# frontplatine_final.net
KiCad netlist of a schematic drawn in EAGLE
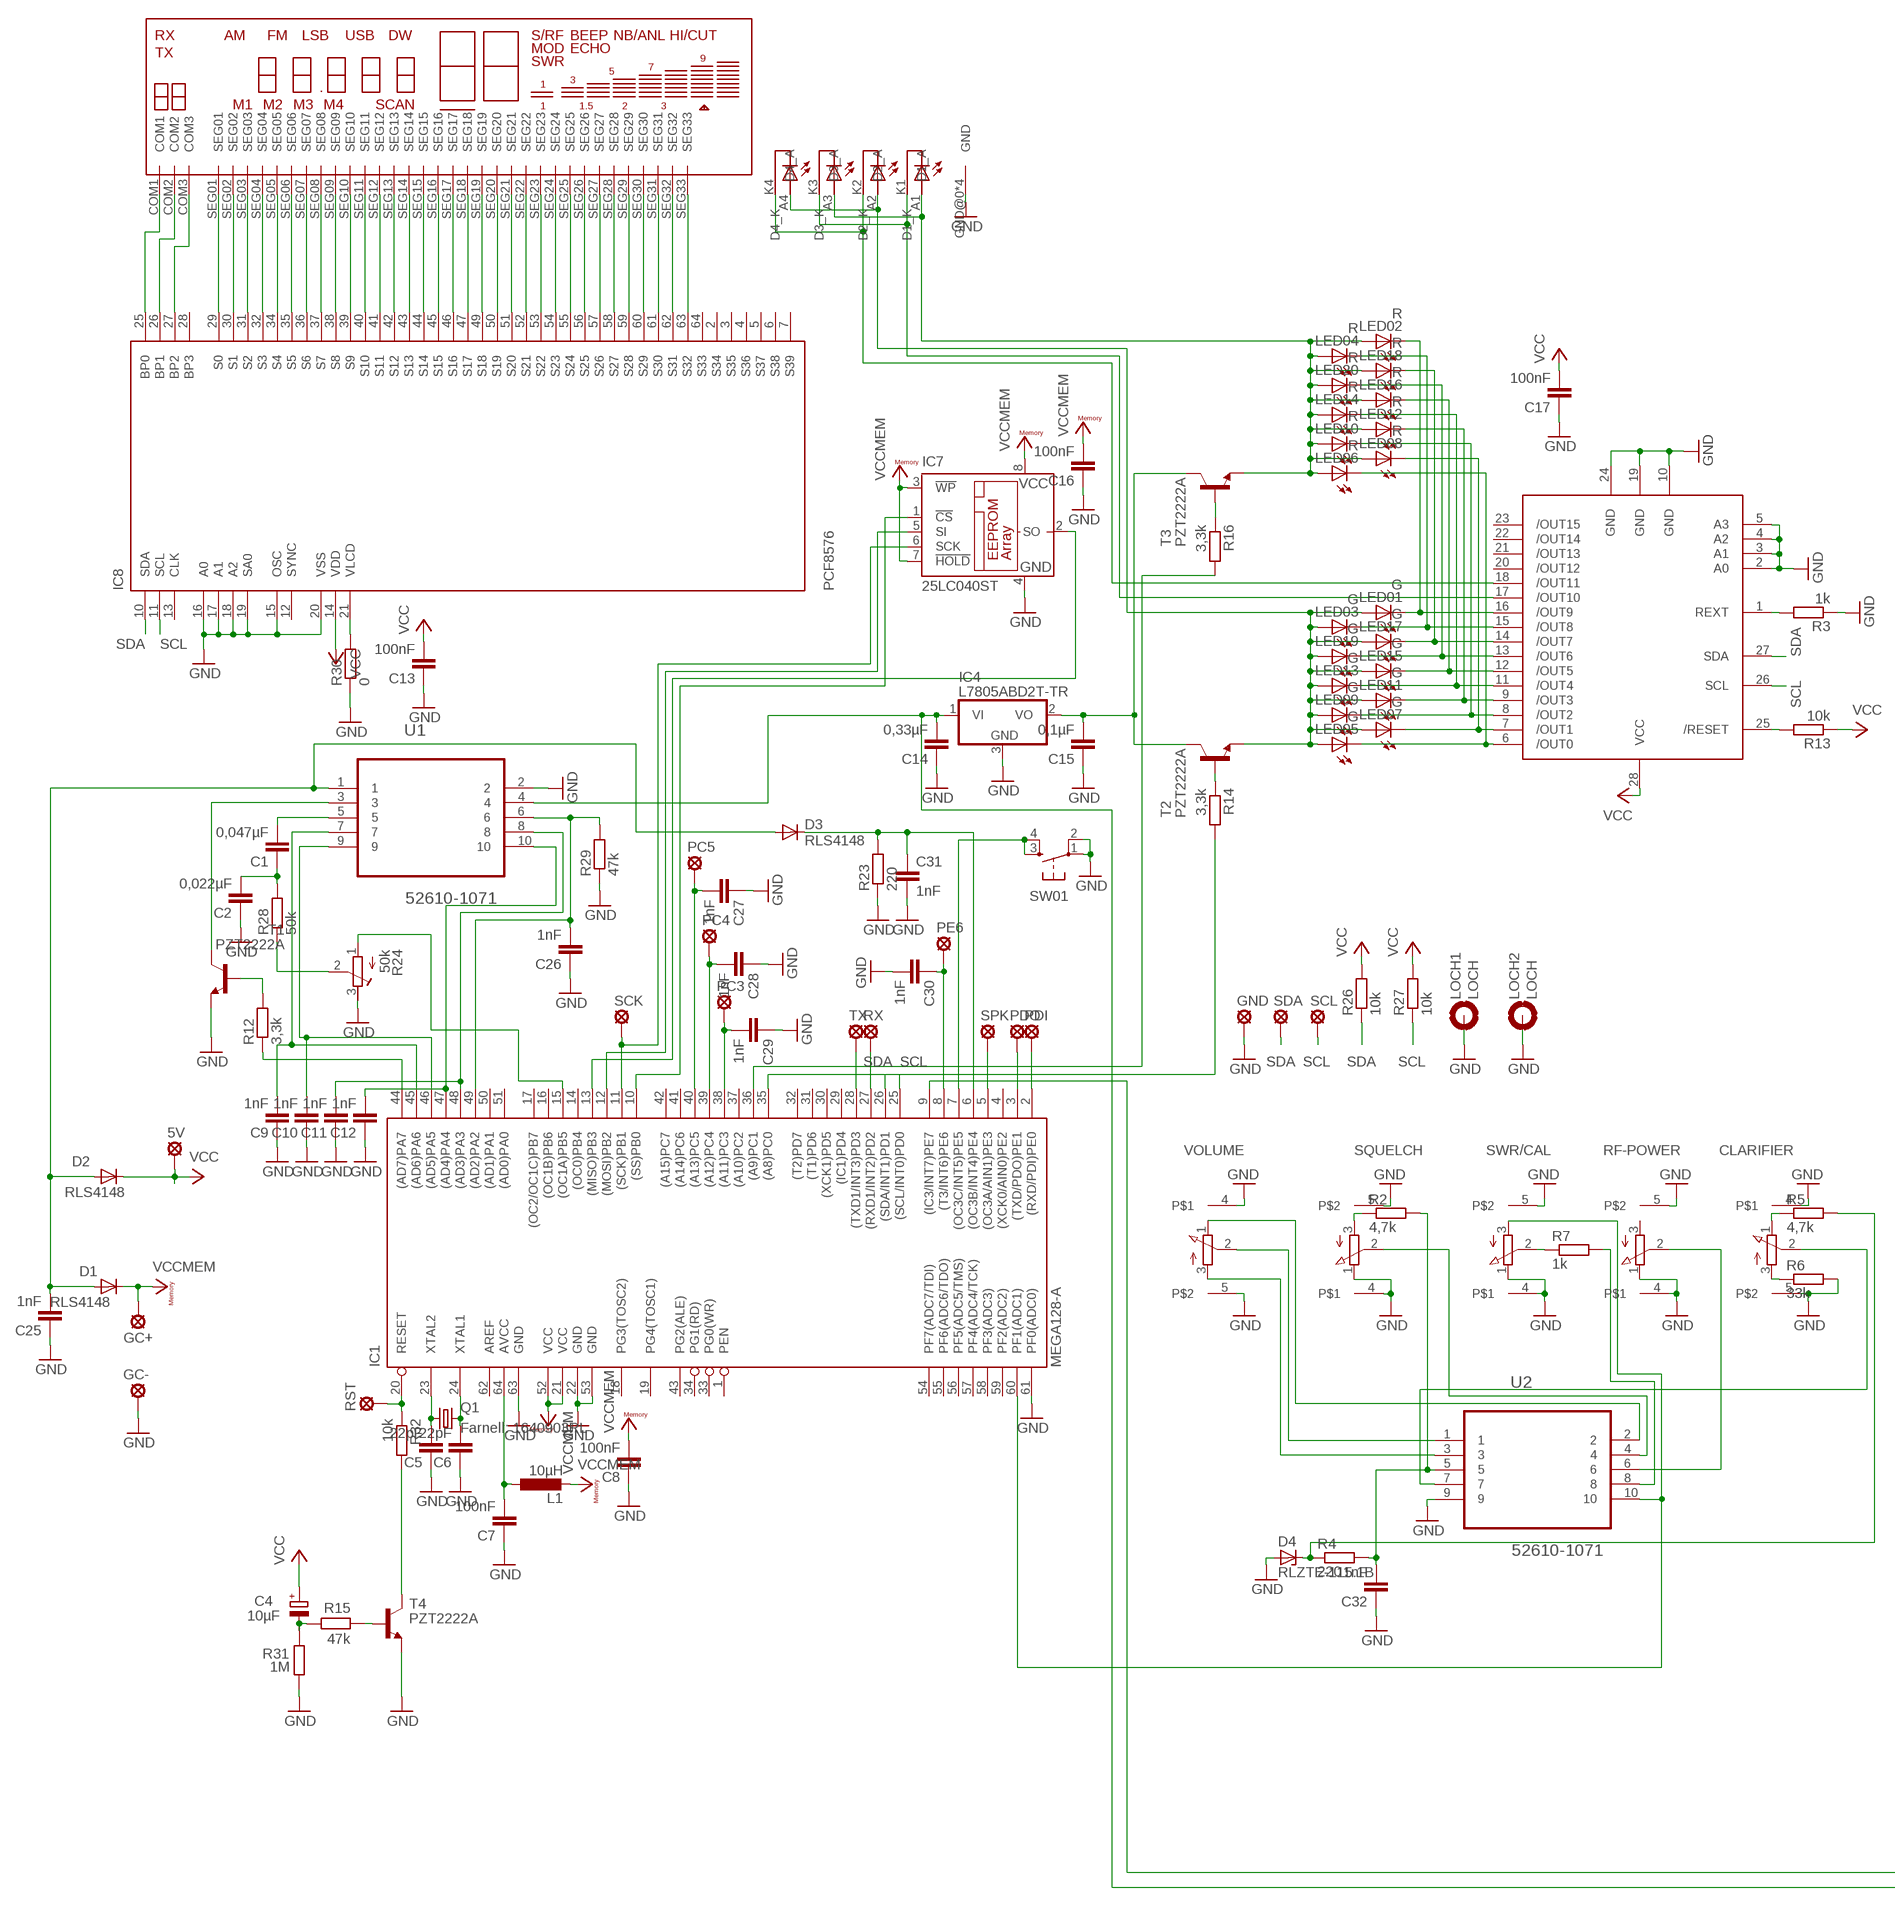
[diagram p0: schematic, sheet 1, part 1 of 2]
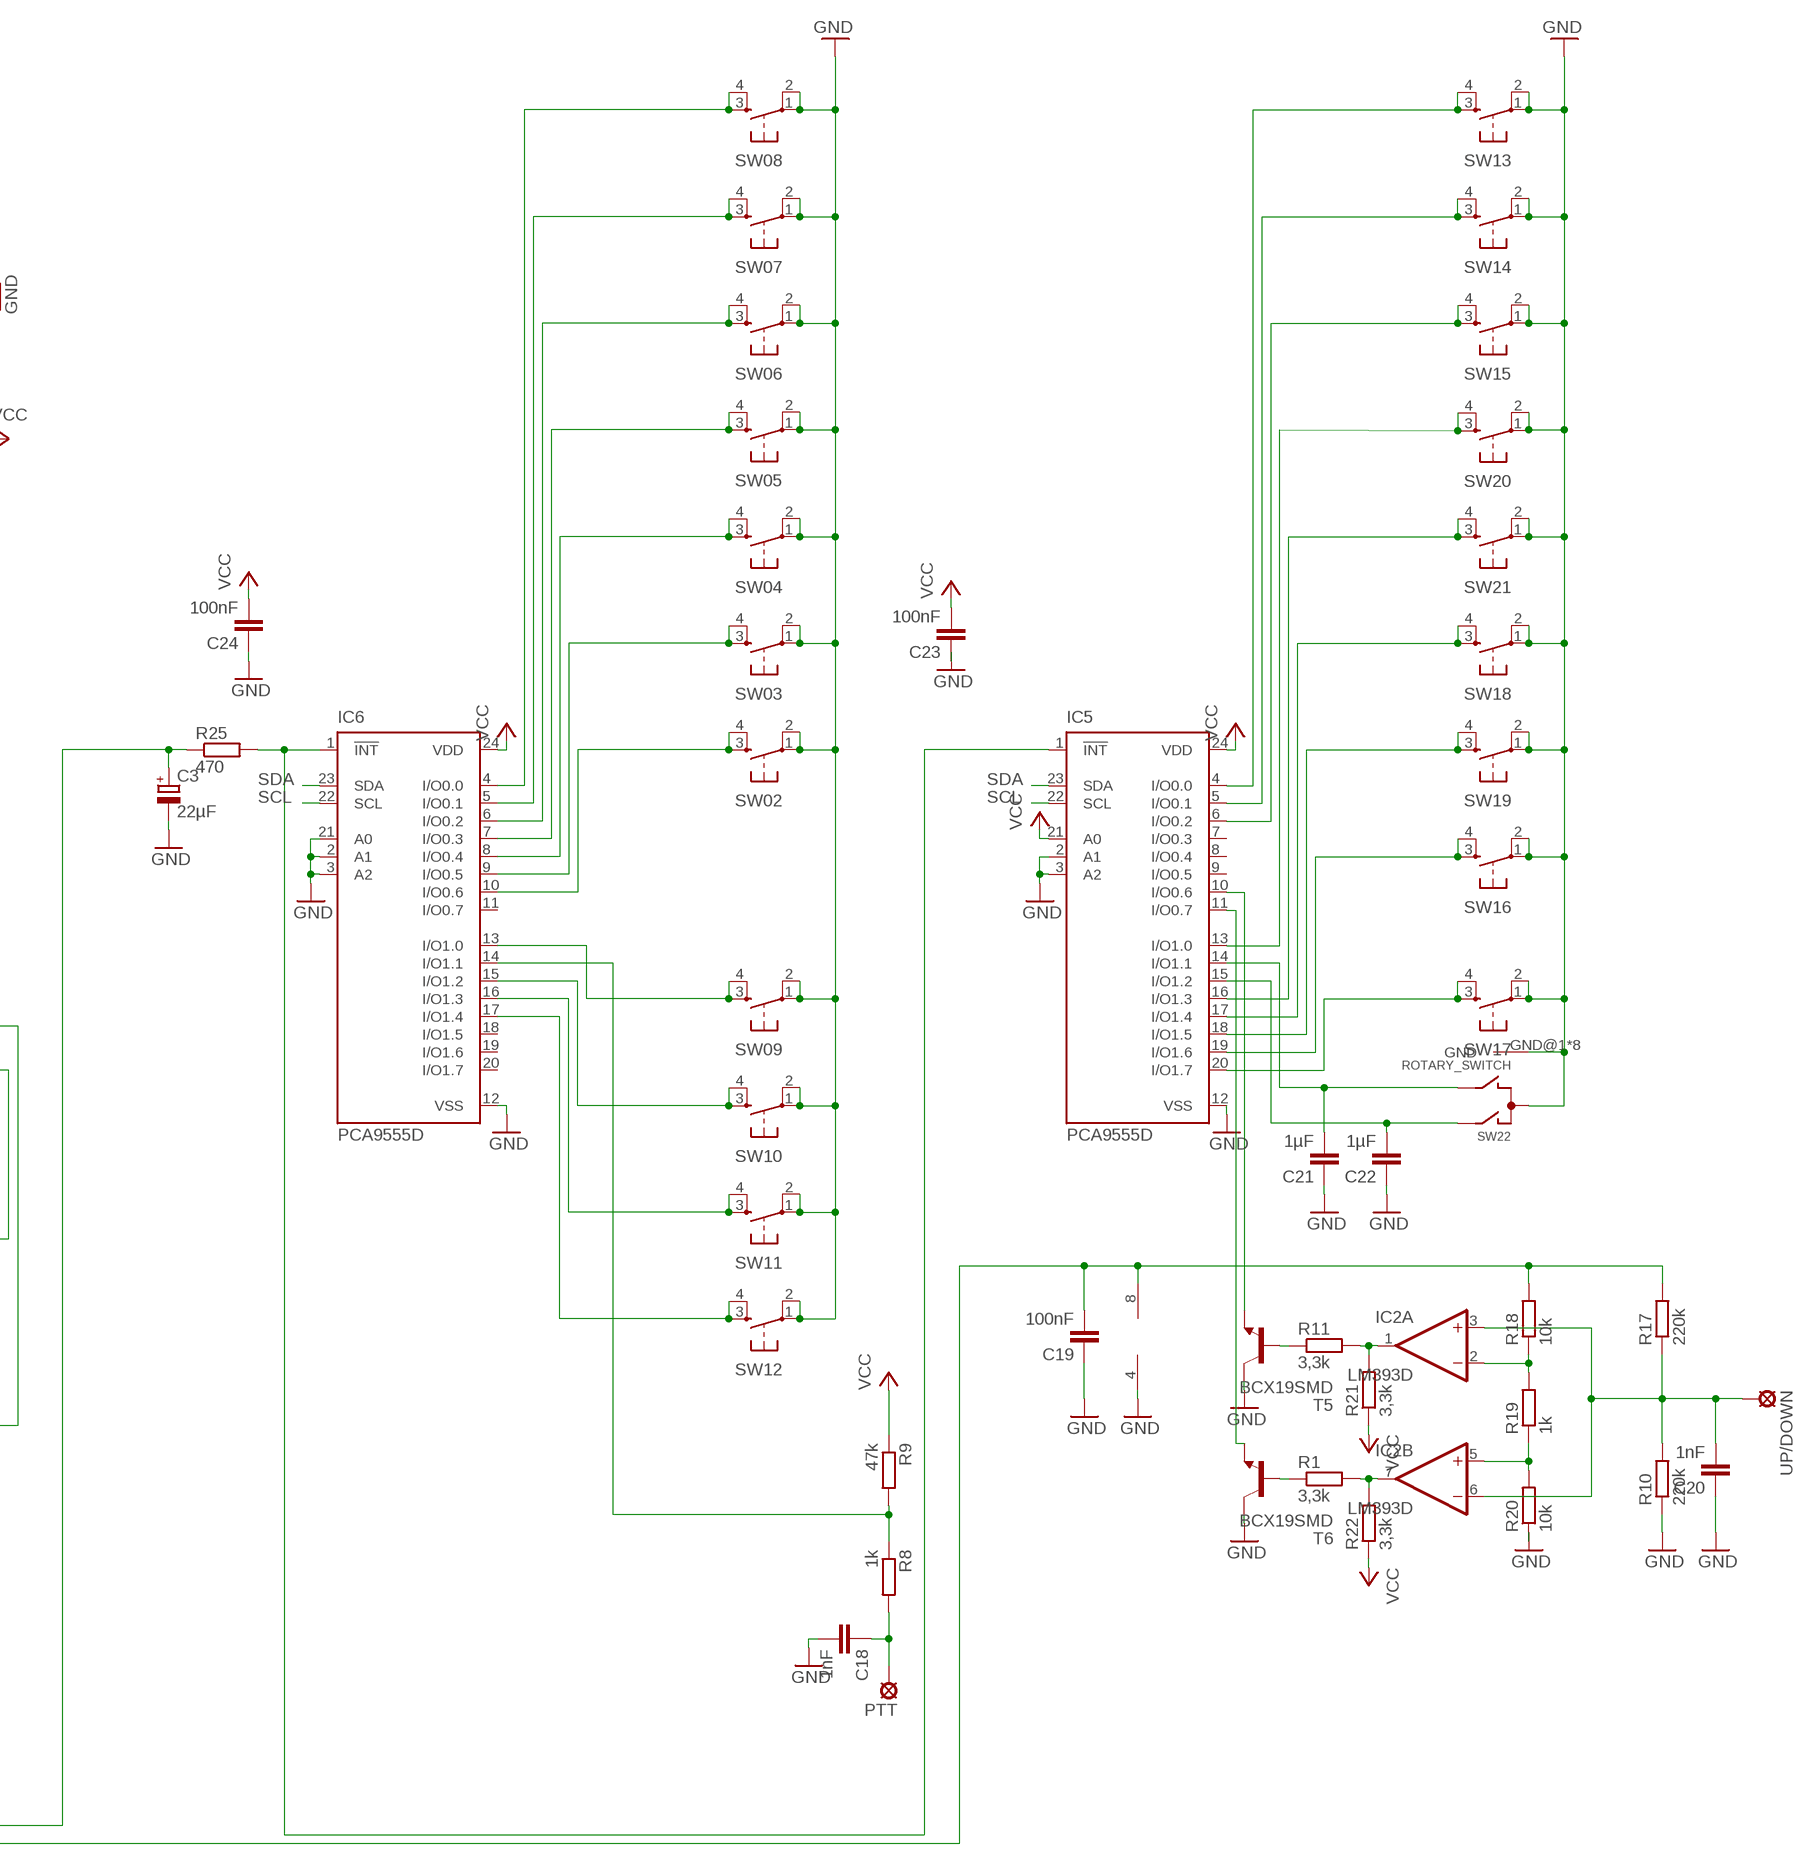
[diagram p1: schematic, sheet 1, part 2 of 2]

(export (version "E")
  (design (tool "Eeschema 10.0.6"))
  (components
    (comp (ref "5V")
      (value "SE11")
      (footprint "eagle-import:SE11")
      (libsource (lib "eagle-import") (part "SE11"))
    )
    (comp (ref "C1")
      (value "0,047µF")
      (footprint "eagle-import:C1206")
      (libsource (lib "eagle-import") (part "C-EUC1206"))
    )
    (comp (ref "C2")
      (value "0,022µF")
      (footprint "eagle-import:C1206")
      (libsource (lib "eagle-import") (part "resistor_C-EUC1206"))
    )
    (comp (ref "C3")
      (value "22µF")
      (footprint "eagle-import:CT3216")
      (libsource (lib "eagle-import") (part "CPOL-EUCT3216"))
    )
    (comp (ref "C4")
      (value "10µF")
      (footprint "eagle-import:CT3216")
      (libsource (lib "eagle-import") (part "CPOL-EUCT3216"))
    )
    (comp (ref "C5")
      (value "22pF")
      (footprint "eagle-import:C1206")
      (libsource (lib "eagle-import") (part "resistor_C-EUC1206"))
    )
    (comp (ref "C6")
      (value "22pF")
      (footprint "eagle-import:C1206")
      (libsource (lib "eagle-import") (part "resistor_C-EUC1206"))
    )
    (comp (ref "C7")
      (value "100nF")
      (footprint "eagle-import:C1206")
      (libsource (lib "eagle-import") (part "resistor_C-EUC1206"))
    )
    (comp (ref "C8")
      (value "100nF")
      (footprint "eagle-import:C1206")
      (libsource (lib "eagle-import") (part "resistor_C-EUC1206"))
    )
    (comp (ref "C9")
      (value "1nF")
      (footprint "eagle-import:C1206")
      (libsource (lib "eagle-import") (part "resistor_C-EUC1206"))
    )
    (comp (ref "C10")
      (value "1nF")
      (footprint "eagle-import:C1206")
      (libsource (lib "eagle-import") (part "resistor_C-EUC1206"))
    )
    (comp (ref "C11")
      (value "1nF")
      (footprint "eagle-import:C1206")
      (libsource (lib "eagle-import") (part "resistor_C-EUC1206"))
    )
    (comp (ref "C12")
      (value "1nF")
      (footprint "eagle-import:C1206")
      (libsource (lib "eagle-import") (part "resistor_C-EUC1206"))
    )
    (comp (ref "C13")
      (value "100nF")
      (footprint "eagle-import:C1206")
      (libsource (lib "eagle-import") (part "resistor_C-EUC1206"))
    )
    (comp (ref "C14")
      (value "0,33µF")
      (footprint "eagle-import:C1206")
      (libsource (lib "eagle-import") (part "resistor_C-EUC1206"))
    )
    (comp (ref "C15")
      (value "0,1µF")
      (footprint "eagle-import:C1206")
      (libsource (lib "eagle-import") (part "resistor_C-EUC1206"))
    )
    (comp (ref "C16")
      (value "100nF")
      (footprint "eagle-import:C1206")
      (libsource (lib "eagle-import") (part "resistor_C-EUC1206"))
    )
    (comp (ref "C17")
      (value "100nF")
      (footprint "eagle-import:C1206")
      (libsource (lib "eagle-import") (part "resistor_C-EUC1206"))
    )
    (comp (ref "C18")
      (value "1nF")
      (footprint "eagle-import:C1206")
      (libsource (lib "eagle-import") (part "resistor_C-EUC1206"))
    )
    (comp (ref "C19")
      (value "100nF")
      (footprint "eagle-import:C1206")
      (libsource (lib "eagle-import") (part "resistor_C-EUC1206"))
    )
    (comp (ref "C20")
      (value "1nF")
      (footprint "eagle-import:C1206")
      (libsource (lib "eagle-import") (part "resistor_C-EUC1206"))
    )
    (comp (ref "C21")
      (value "1µF")
      (footprint "eagle-import:C1206")
      (libsource (lib "eagle-import") (part "resistor_C-EUC1206"))
    )
    (comp (ref "C22")
      (value "1µF")
      (footprint "eagle-import:C1206")
      (libsource (lib "eagle-import") (part "resistor_C-EUC1206"))
    )
    (comp (ref "C23")
      (value "100nF")
      (footprint "eagle-import:C1206")
      (libsource (lib "eagle-import") (part "resistor_C-EUC1206"))
    )
    (comp (ref "C24")
      (value "100nF")
      (footprint "eagle-import:C1206")
      (libsource (lib "eagle-import") (part "resistor_C-EUC1206"))
    )
    (comp (ref "C25")
      (value "1nF")
      (footprint "eagle-import:C1206")
      (libsource (lib "eagle-import") (part "resistor_C-EUC1206"))
    )
    (comp (ref "C26")
      (value "1nF")
      (footprint "eagle-import:C1206")
      (libsource (lib "eagle-import") (part "resistor_C-EUC1206"))
    )
    (comp (ref "C27")
      (value "1nF")
      (footprint "eagle-import:C1206")
      (libsource (lib "eagle-import") (part "resistor_C-EUC1206"))
    )
    (comp (ref "C28")
      (value "1nF")
      (footprint "eagle-import:C1206")
      (libsource (lib "eagle-import") (part "resistor_C-EUC1206"))
    )
    (comp (ref "C29")
      (value "1nF")
      (footprint "eagle-import:C1206")
      (libsource (lib "eagle-import") (part "resistor_C-EUC1206"))
    )
    (comp (ref "C30")
      (value "1nF")
      (footprint "eagle-import:C1206")
      (libsource (lib "eagle-import") (part "resistor_C-EUC1206"))
    )
    (comp (ref "C31")
      (value "1nF")
      (footprint "eagle-import:C1206")
      (libsource (lib "eagle-import") (part "resistor_C-EUC1206"))
    )
    (comp (ref "C32")
      (value "1nF")
      (footprint "eagle-import:C1206")
      (libsource (lib "eagle-import") (part "resistor_C-EUC1206"))
    )
    (comp (ref "CLARIFIER")
      (value "POTI")
      (footprint "eagle-import:POTI")
      (libsource (lib "eagle-import") (part "POTI"))
    )
    (comp (ref "D1")
      (value "RLS4148")
      (footprint "eagle-import:SOD80C")
      (libsource (lib "eagle-import") (part "DIODE-SOD80C"))
    )
    (comp (ref "D2")
      (value "RLS4148")
      (footprint "eagle-import:SOD80C")
      (libsource (lib "eagle-import") (part "DIODE-SOD80C"))
    )
    (comp (ref "D3")
      (value "RLS4148")
      (footprint "eagle-import:SOD80C")
      (libsource (lib "eagle-import") (part "DIODE-SOD80C"))
    )
    (comp (ref "D4")
      (value "RLZTE-115.1B")
      (footprint "eagle-import:SOD80C")
      (libsource (lib "eagle-import") (part "ZENER-DIODESOD80C"))
    )
    (comp (ref "DISPLAY1")
      (value "DISPLAY")
      (footprint "eagle-import:DISPLAY")
      (libsource (lib "eagle-import") (part "DISPLAY"))
    )
    (comp (ref "GC+")
      (value "SE11")
      (footprint "eagle-import:SE11")
      (libsource (lib "eagle-import") (part "SE11"))
    )
    (comp (ref "GC-")
      (value "SE11")
      (footprint "eagle-import:SE11")
      (libsource (lib "eagle-import") (part "SE11"))
    )
    (comp (ref "GND")
      (value "SE11")
      (footprint "eagle-import:SE11")
      (libsource (lib "eagle-import") (part "SE11"))
    )
    (comp (ref "IC1")
      (value "MEGA128-A")
      (footprint "eagle-import:TQFP64")
      (fields (field (name "MPN") "ATMEGA128-16AU"))
      (libsource (lib "eagle-import") (part "MEGA128-A"))
    )
    (comp (ref "IC2")
      (value "LM393D")
      (footprint "eagle-import:SO08")
      (libsource (lib "eagle-import") (part "LM393D"))
    )
    (comp (ref "IC3")
      (value "TLC59116")
      (footprint "eagle-import:TSSOP28")
      (libsource (lib "eagle-import") (part "TLC59116"))
    )
    (comp (ref "IC4")
      (value "L7805ABD2T-TR")
      (footprint "eagle-import:TO252")
      (libsource (lib "eagle-import") (part "78DT05"))
    )
    (comp (ref "IC5")
      (value "PCA9555D")
      (footprint "eagle-import:SO24")
      (fields (field (name "MPN") "PCA9555DW"))
      (libsource (lib "eagle-import") (part "PCA9555D"))
    )
    (comp (ref "IC6")
      (value "PCA9555D")
      (footprint "eagle-import:SO24")
      (fields (field (name "MPN") "PCA9555DW"))
      (libsource (lib "eagle-import") (part "PCA9555D"))
    )
    (comp (ref "IC7")
      (value "25LC040ST")
      (footprint "eagle-import:TSSOP8")
      (fields (field (name "MF") "MICROCHIP") (field (name "MPN") "25LC040A-I/ST"))
      (libsource (lib "eagle-import") (part "25STLC040"))
    )
    (comp (ref "IC8")
      (value "PCF8576")
      (footprint "eagle-import:64LQFP")
      (libsource (lib "eagle-import") (part "PCF8576"))
    )
    (comp (ref "L1")
      (value "10µH")
      (footprint "eagle-import:L1812")
      (libsource (lib "eagle-import") (part "L-EUL1812"))
    )
    (comp (ref "LED01")
      (value "G")
      (footprint "eagle-import:CHIPLED_1206")
      (libsource (lib "eagle-import") (part "LEDCHIPLED_1206"))
    )
    (comp (ref "LED02")
      (value "R")
      (footprint "eagle-import:CHIPLED_1206")
      (libsource (lib "eagle-import") (part "LEDCHIPLED_1206"))
    )
    (comp (ref "LED03")
      (value "G")
      (footprint "eagle-import:CHIPLED_1206")
      (libsource (lib "eagle-import") (part "LEDCHIPLED_1206"))
    )
    (comp (ref "LED04")
      (value "R")
      (footprint "eagle-import:CHIPLED_1206")
      (libsource (lib "eagle-import") (part "LEDCHIPLED_1206"))
    )
    (comp (ref "LED05")
      (value "G")
      (footprint "eagle-import:CHIPLED_1206")
      (libsource (lib "eagle-import") (part "LEDCHIPLED_1206"))
    )
    (comp (ref "LED06")
      (value "R")
      (footprint "eagle-import:CHIPLED_1206")
      (libsource (lib "eagle-import") (part "LEDCHIPLED_1206"))
    )
    (comp (ref "LED07")
      (value "G")
      (footprint "eagle-import:CHIPLED_1206")
      (libsource (lib "eagle-import") (part "LEDCHIPLED_1206"))
    )
    (comp (ref "LED08")
      (value "R")
      (footprint "eagle-import:CHIPLED_1206")
      (libsource (lib "eagle-import") (part "LEDCHIPLED_1206"))
    )
    (comp (ref "LED09")
      (value "G")
      (footprint "eagle-import:CHIPLED_1206")
      (libsource (lib "eagle-import") (part "LEDCHIPLED_1206"))
    )
    (comp (ref "LED10")
      (value "R")
      (footprint "eagle-import:CHIPLED_1206")
      (libsource (lib "eagle-import") (part "LEDCHIPLED_1206"))
    )
    (comp (ref "LED11")
      (value "G")
      (footprint "eagle-import:CHIPLED_1206")
      (libsource (lib "eagle-import") (part "LEDCHIPLED_1206"))
    )
    (comp (ref "LED12")
      (value "R")
      (footprint "eagle-import:CHIPLED_1206")
      (libsource (lib "eagle-import") (part "LEDCHIPLED_1206"))
    )
    (comp (ref "LED13")
      (value "G")
      (footprint "eagle-import:CHIPLED_1206")
      (libsource (lib "eagle-import") (part "LEDCHIPLED_1206"))
    )
    (comp (ref "LED14")
      (value "R")
      (footprint "eagle-import:CHIPLED_1206")
      (libsource (lib "eagle-import") (part "LEDCHIPLED_1206"))
    )
    (comp (ref "LED15")
      (value "G")
      (footprint "eagle-import:CHIPLED_1206")
      (libsource (lib "eagle-import") (part "LEDCHIPLED_1206"))
    )
    (comp (ref "LED16")
      (value "R")
      (footprint "eagle-import:CHIPLED_1206")
      (libsource (lib "eagle-import") (part "LEDCHIPLED_1206"))
    )
    (comp (ref "LED17")
      (value "G")
      (footprint "eagle-import:CHIPLED_1206")
      (libsource (lib "eagle-import") (part "LEDCHIPLED_1206"))
    )
    (comp (ref "LED18")
      (value "R")
      (footprint "eagle-import:CHIPLED_1206")
      (libsource (lib "eagle-import") (part "LEDCHIPLED_1206"))
    )
    (comp (ref "LED19")
      (value "G")
      (footprint "eagle-import:CHIPLED_1206")
      (libsource (lib "eagle-import") (part "LEDCHIPLED_1206"))
    )
    (comp (ref "LED20")
      (value "R")
      (footprint "eagle-import:CHIPLED_1206")
      (libsource (lib "eagle-import") (part "LEDCHIPLED_1206"))
    )
    (comp (ref "LOCH1")
      (value "LOCH")
      (footprint "eagle-import:LOCH")
      (libsource (lib "eagle-import") (part "LOCH"))
    )
    (comp (ref "LOCH2")
      (value "LOCH")
      (footprint "eagle-import:LOCH")
      (libsource (lib "eagle-import") (part "LOCH"))
    )
    (comp (ref "PC3")
      (value "SE11")
      (footprint "eagle-import:SE11")
      (libsource (lib "eagle-import") (part "SE11"))
    )
    (comp (ref "PC4")
      (value "SE11")
      (footprint "eagle-import:SE11")
      (libsource (lib "eagle-import") (part "SE11"))
    )
    (comp (ref "PC5")
      (value "SE11")
      (footprint "eagle-import:SE11")
      (libsource (lib "eagle-import") (part "SE11"))
    )
    (comp (ref "PDI")
      (value "SE11")
      (footprint "eagle-import:SE11")
      (libsource (lib "eagle-import") (part "SE11"))
    )
    (comp (ref "PDO")
      (value "SE11")
      (footprint "eagle-import:SE11")
      (libsource (lib "eagle-import") (part "SE11"))
    )
    (comp (ref "PE6")
      (value "SE11")
      (footprint "eagle-import:SE11")
      (libsource (lib "eagle-import") (part "SE11"))
    )
    (comp (ref "PTT")
      (value "SE11")
      (footprint "eagle-import:SE11")
      (libsource (lib "eagle-import") (part "SE11"))
    )
    (comp (ref "Q1")
      (value "Farnell: 1640903RL")
      (footprint "eagle-import:HC49UP")
      (libsource (lib "eagle-import") (part "CRYSTALHC49UP"))
    )
    (comp (ref "R1")
      (value "3,3k")
      (footprint "eagle-import:R1206")
      (libsource (lib "eagle-import") (part "resistor_R-EU_R1206"))
    )
    (comp (ref "R2")
      (value "4,7k")
      (footprint "eagle-import:R1206")
      (libsource (lib "eagle-import") (part "resistor_R-EU_R1206"))
    )
    (comp (ref "R3")
      (value "1k")
      (footprint "eagle-import:R1206")
      (libsource (lib "eagle-import") (part "R-EU_R1206"))
    )
    (comp (ref "R4")
      (value "220")
      (footprint "eagle-import:R1206")
      (libsource (lib "eagle-import") (part "resistor_R-EU_R1206"))
    )
    (comp (ref "R5")
      (value "4,7k")
      (footprint "eagle-import:R1206")
      (libsource (lib "eagle-import") (part "resistor_R-EU_R1206"))
    )
    (comp (ref "R6")
      (value "33k")
      (footprint "eagle-import:R1206")
      (libsource (lib "eagle-import") (part "resistor_R-EU_R1206"))
    )
    (comp (ref "R7")
      (value "1k")
      (footprint "eagle-import:R1206")
      (libsource (lib "eagle-import") (part "resistor_R-EU_R1206"))
    )
    (comp (ref "R8")
      (value "1k")
      (footprint "eagle-import:R1206")
      (libsource (lib "eagle-import") (part "resistor_R-EU_R1206"))
    )
    (comp (ref "R9")
      (value "47k")
      (footprint "eagle-import:R1206")
      (libsource (lib "eagle-import") (part "resistor_R-EU_R1206"))
    )
    (comp (ref "R10")
      (value "220k")
      (footprint "eagle-import:R1206")
      (libsource (lib "eagle-import") (part "resistor_R-EU_R1206"))
    )
    (comp (ref "R11")
      (value "3,3k")
      (footprint "eagle-import:R1206")
      (libsource (lib "eagle-import") (part "resistor_R-EU_R1206"))
    )
    (comp (ref "R12")
      (value "3,3k")
      (footprint "eagle-import:R1206")
      (libsource (lib "eagle-import") (part "resistor_R-EU_R1206"))
    )
    (comp (ref "R13")
      (value "10k")
      (footprint "eagle-import:R1206")
      (libsource (lib "eagle-import") (part "resistor_R-EU_R1206"))
    )
    (comp (ref "R14")
      (value "3,3k")
      (footprint "eagle-import:R1206")
      (libsource (lib "eagle-import") (part "resistor_R-EU_R1206"))
    )
    (comp (ref "R15")
      (value "47k")
      (footprint "eagle-import:R1206")
      (libsource (lib "eagle-import") (part "resistor_R-EU_R1206"))
    )
    (comp (ref "R16")
      (value "3,3k")
      (footprint "eagle-import:R1206")
      (libsource (lib "eagle-import") (part "resistor_R-EU_R1206"))
    )
    (comp (ref "R17")
      (value "220k")
      (footprint "eagle-import:R1206")
      (libsource (lib "eagle-import") (part "resistor_R-EU_R1206"))
    )
    (comp (ref "R18")
      (value "10k")
      (footprint "eagle-import:R1206")
      (libsource (lib "eagle-import") (part "resistor_R-EU_R1206"))
    )
    (comp (ref "R19")
      (value "1k")
      (footprint "eagle-import:R1206")
      (libsource (lib "eagle-import") (part "resistor_R-EU_R1206"))
    )
    (comp (ref "R20")
      (value "10k")
      (footprint "eagle-import:R1206")
      (libsource (lib "eagle-import") (part "resistor_R-EU_R1206"))
    )
    (comp (ref "R21")
      (value "3,3k")
      (footprint "eagle-import:R1206")
      (libsource (lib "eagle-import") (part "resistor_R-EU_R1206"))
    )
    (comp (ref "R22")
      (value "3,3k")
      (footprint "eagle-import:R1206")
      (libsource (lib "eagle-import") (part "resistor_R-EU_R1206"))
    )
    (comp (ref "R23")
      (value "220")
      (footprint "eagle-import:R1206")
      (libsource (lib "eagle-import") (part "resistor_R-EU_R1206"))
    )
    (comp (ref "R24")
      (value "50k")
      (footprint "eagle-import:RTRIM3314J")
      (libsource (lib "eagle-import") (part "R-TRIMM3314J"))
    )
    (comp (ref "R25")
      (value "470")
      (footprint "eagle-import:R1206")
      (libsource (lib "eagle-import") (part "resistor_R-EU_R1206"))
    )
    (comp (ref "R26")
      (value "10k")
      (footprint "eagle-import:R1206")
      (libsource (lib "eagle-import") (part "resistor_R-EU_R1206"))
    )
    (comp (ref "R27")
      (value "10k")
      (footprint "eagle-import:R1206")
      (libsource (lib "eagle-import") (part "resistor_R-EU_R1206"))
    )
    (comp (ref "R28")
      (value "50k")
      (footprint "eagle-import:R1206")
      (libsource (lib "eagle-import") (part "resistor_R-EU_R1206"))
    )
    (comp (ref "R29")
      (value "47k")
      (footprint "eagle-import:R1206")
      (libsource (lib "eagle-import") (part "resistor_R-EU_R1206"))
    )
    (comp (ref "R30")
      (value "0")
      (footprint "eagle-import:R1206")
      (libsource (lib "eagle-import") (part "resistor_R-EU_R1206"))
    )
    (comp (ref "R31")
      (value "1M")
      (footprint "eagle-import:R1206")
      (libsource (lib "eagle-import") (part "resistor_R-EU_R1206"))
    )
    (comp (ref "R32")
      (value "10k")
      (footprint "eagle-import:R1206")
      (libsource (lib "eagle-import") (part "resistor_R-EU_R1206"))
    )
    (comp (ref "RF-POWER")
      (value "POTI")
      (footprint "eagle-import:POTI")
      (libsource (lib "eagle-import") (part "POTI"))
    )
    (comp (ref "RST")
      (value "SE11")
      (footprint "eagle-import:SE11")
      (libsource (lib "eagle-import") (part "SE11"))
    )
    (comp (ref "RX")
      (value "SE11")
      (footprint "eagle-import:SE11")
      (libsource (lib "eagle-import") (part "SE11"))
    )
    (comp (ref "SCK")
      (value "SE11")
      (footprint "eagle-import:SE11")
      (libsource (lib "eagle-import") (part "SE11"))
    )
    (comp (ref "SCL")
      (value "SE11")
      (footprint "eagle-import:SE11")
      (libsource (lib "eagle-import") (part "SE11"))
    )
    (comp (ref "SDA")
      (value "SE11")
      (footprint "eagle-import:SE11")
      (libsource (lib "eagle-import") (part "SE11"))
    )
    (comp (ref "SPK")
      (value "SE11")
      (footprint "eagle-import:SE11")
      (libsource (lib "eagle-import") (part "SE11"))
    )
    (comp (ref "SQUELCH")
      (value "POTI")
      (footprint "eagle-import:POTI")
      (libsource (lib "eagle-import") (part "POTI"))
    )
    (comp (ref "SW01")
      (value "TASTER")
      (footprint "eagle-import:TASTER")
      (libsource (lib "eagle-import") (part "TASTER"))
    )
    (comp (ref "SW02")
      (value "TASTER")
      (footprint "eagle-import:TASTER")
      (libsource (lib "eagle-import") (part "TASTER"))
    )
    (comp (ref "SW03")
      (value "TASTER")
      (footprint "eagle-import:TASTER")
      (libsource (lib "eagle-import") (part "TASTER"))
    )
    (comp (ref "SW04")
      (value "TASTER")
      (footprint "eagle-import:TASTER")
      (libsource (lib "eagle-import") (part "TASTER"))
    )
    (comp (ref "SW05")
      (value "TASTER")
      (footprint "eagle-import:TASTER")
      (libsource (lib "eagle-import") (part "TASTER"))
    )
    (comp (ref "SW06")
      (value "TASTER")
      (footprint "eagle-import:TASTER")
      (libsource (lib "eagle-import") (part "TASTER"))
    )
    (comp (ref "SW07")
      (value "TASTER")
      (footprint "eagle-import:TASTER")
      (libsource (lib "eagle-import") (part "TASTER"))
    )
    (comp (ref "SW08")
      (value "TASTER")
      (footprint "eagle-import:TASTER")
      (libsource (lib "eagle-import") (part "TASTER"))
    )
    (comp (ref "SW09")
      (value "TASTER")
      (footprint "eagle-import:TASTER")
      (libsource (lib "eagle-import") (part "TASTER"))
    )
    (comp (ref "SW10")
      (value "TASTER")
      (footprint "eagle-import:TASTER")
      (libsource (lib "eagle-import") (part "TASTER"))
    )
    (comp (ref "SW11")
      (value "TASTER")
      (footprint "eagle-import:TASTER")
      (libsource (lib "eagle-import") (part "TASTER"))
    )
    (comp (ref "SW12")
      (value "TASTER")
      (footprint "eagle-import:TASTER")
      (libsource (lib "eagle-import") (part "TASTER"))
    )
    (comp (ref "SW13")
      (value "TASTER")
      (footprint "eagle-import:TASTER")
      (libsource (lib "eagle-import") (part "TASTER"))
    )
    (comp (ref "SW14")
      (value "TASTER")
      (footprint "eagle-import:TASTER")
      (libsource (lib "eagle-import") (part "TASTER"))
    )
    (comp (ref "SW15")
      (value "TASTER")
      (footprint "eagle-import:TASTER")
      (libsource (lib "eagle-import") (part "TASTER"))
    )
    (comp (ref "SW16")
      (value "TASTER")
      (footprint "eagle-import:TASTER")
      (libsource (lib "eagle-import") (part "TASTER"))
    )
    (comp (ref "SW17")
      (value "TASTER")
      (footprint "eagle-import:TASTER")
      (libsource (lib "eagle-import") (part "TASTER"))
    )
    (comp (ref "SW18")
      (value "TASTER")
      (footprint "eagle-import:TASTER")
      (libsource (lib "eagle-import") (part "TASTER"))
    )
    (comp (ref "SW19")
      (value "TASTER")
      (footprint "eagle-import:TASTER")
      (libsource (lib "eagle-import") (part "TASTER"))
    )
    (comp (ref "SW20")
      (value "TASTER")
      (footprint "eagle-import:TASTER")
      (libsource (lib "eagle-import") (part "TASTER"))
    )
    (comp (ref "SW21")
      (value "TASTER")
      (footprint "eagle-import:TASTER")
      (libsource (lib "eagle-import") (part "TASTER"))
    )
    (comp (ref "SW22")
      (value "ROTARY_SWITCH")
      (footprint "eagle-import:ROTARY_SWITCH")
      (libsource (lib "eagle-import") (part "ROTARY_SWITCH"))
    )
    (comp (ref "SWR/CAL")
      (value "POTI")
      (footprint "eagle-import:POTI")
      (libsource (lib "eagle-import") (part "POTI"))
    )
    (comp (ref "T1")
      (value "PZT2222A")
      (footprint "eagle-import:SOT223")
      (libsource (lib "eagle-import") (part "-NPN-SOT223PZT2222A"))
    )
    (comp (ref "T2")
      (value "PZT2222A")
      (footprint "eagle-import:SOT223")
      (libsource (lib "eagle-import") (part "-NPN-SOT223PZT2222A"))
    )
    (comp (ref "T3")
      (value "PZT2222A")
      (footprint "eagle-import:SOT223")
      (libsource (lib "eagle-import") (part "-NPN-SOT223PZT2222A"))
    )
    (comp (ref "T4")
      (value "PZT2222A")
      (footprint "eagle-import:SOT223")
      (libsource (lib "eagle-import") (part "-NPN-SOT223PZT2222A"))
    )
    (comp (ref "T5")
      (value "BCX19SMD")
      (footprint "eagle-import:SOT23-BEC")
      (libsource (lib "eagle-import") (part "BCX19SMD"))
    )
    (comp (ref "T6")
      (value "BCX19SMD")
      (footprint "eagle-import:SOT23-BEC")
      (libsource (lib "eagle-import") (part "BCX19SMD"))
    )
    (comp (ref "TX")
      (value "SE11")
      (footprint "eagle-import:SE11")
      (libsource (lib "eagle-import") (part "SE11"))
    )
    (comp (ref "U1")
      (value "52610-1071")
      (footprint "eagle-import:MOLEX_52610-1071")
      (libsource (lib "eagle-import") (part "52610-1071"))
    )
    (comp (ref "U2")
      (value "52610-1071")
      (footprint "eagle-import:MOLEX_52610-1071")
      (libsource (lib "eagle-import") (part "52610-1071"))
    )
    (comp (ref "UP/DOWN")
      (value "SE11")
      (footprint "eagle-import:SE11")
      (libsource (lib "eagle-import") (part "SE11"))
    )
    (comp (ref "VOLUME")
      (value "POTI")
      (footprint "eagle-import:POTI")
      (libsource (lib "eagle-import") (part "POTI"))
    )
  )
  (nets
    (net (code "1") (name "/SCL") (class "Default")
      (node (ref "IC1") (pin "25") (pinfunction "(SCL/INT0)PD0_25") (pintype "bidirectional"))
      (node (ref "IC3") (pin "26") (pinfunction "SCL_26") (pintype "bidirectional"))
      (node (ref "IC5") (pin "22") (pinfunction "SCL_22") (pintype "input"))
      (node (ref "IC6") (pin "22") (pinfunction "SCL_22") (pintype "input"))
      (node (ref "IC8") (pin "11") (pinfunction "SCL_11") (pintype "input"))
      (node (ref "R27") (pin "1") (pinfunction "1_1") (pintype "passive"))
      (node (ref "SCL") (pin "MP") (pinfunction "MP_MP") (pintype "passive"))
    )
    (net (code "2") (name "/SDA") (class "Default")
      (node (ref "IC1") (pin "26") (pinfunction "(SDA/INT1)PD1_26") (pintype "bidirectional"))
      (node (ref "IC3") (pin "27") (pinfunction "SDA_27") (pintype "bidirectional"))
      (node (ref "IC5") (pin "23") (pinfunction "SDA_23") (pintype "bidirectional"))
      (node (ref "IC6") (pin "23") (pinfunction "SDA_23") (pintype "bidirectional"))
      (node (ref "IC8") (pin "10") (pinfunction "SDA_10") (pintype "bidirectional"))
      (node (ref "R26") (pin "1") (pinfunction "1_1") (pintype "passive"))
      (node (ref "SDA") (pin "MP") (pinfunction "MP_MP") (pintype "passive"))
    )
    (net (code "3") (name "GND") (class "Default")
      (node (ref "C10") (pin "1") (pinfunction "1_1") (pintype "passive"))
      (node (ref "C11") (pin "1") (pinfunction "1_1") (pintype "passive"))
      (node (ref "C12") (pin "1") (pinfunction "1_1") (pintype "passive"))
      (node (ref "C13") (pin "1") (pinfunction "1_1") (pintype "passive"))
      (node (ref "C14") (pin "1") (pinfunction "1_1") (pintype "passive"))
      (node (ref "C15") (pin "1") (pinfunction "1_1") (pintype "passive"))
      (node (ref "C16") (pin "1") (pinfunction "1_1") (pintype "passive"))
      (node (ref "C17") (pin "1") (pinfunction "1_1") (pintype "passive"))
      (node (ref "C18") (pin "2") (pinfunction "2_2") (pintype "passive"))
      (node (ref "C19") (pin "1") (pinfunction "1_1") (pintype "passive"))
      (node (ref "C2") (pin "1") (pinfunction "1_1") (pintype "passive"))
      (node (ref "C20") (pin "1") (pinfunction "1_1") (pintype "passive"))
      (node (ref "C21") (pin "1") (pinfunction "1_1") (pintype "passive"))
      (node (ref "C22") (pin "1") (pinfunction "1_1") (pintype "passive"))
      (node (ref "C23") (pin "1") (pinfunction "1_1") (pintype "passive"))
      (node (ref "C24") (pin "1") (pinfunction "1_1") (pintype "passive"))
      (node (ref "C25") (pin "1") (pinfunction "1_1") (pintype "passive"))
      (node (ref "C26") (pin "1") (pinfunction "1_1") (pintype "passive"))
      (node (ref "C27") (pin "1") (pinfunction "1_1") (pintype "passive"))
      (node (ref "C28") (pin "1") (pinfunction "1_1") (pintype "passive"))
      (node (ref "C29") (pin "1") (pinfunction "1_1") (pintype "passive"))
      (node (ref "C3") (pin "-") (pinfunction "-_-") (pintype "passive"))
      (node (ref "C30") (pin "2") (pinfunction "2_2") (pintype "passive"))
      (node (ref "C31") (pin "2") (pinfunction "2_2") (pintype "passive"))
      (node (ref "C32") (pin "1") (pinfunction "1_1") (pintype "passive"))
      (node (ref "C5") (pin "1") (pinfunction "1_1") (pintype "passive"))
      (node (ref "C6") (pin "1") (pinfunction "1_1") (pintype "passive"))
      (node (ref "C7") (pin "1") (pinfunction "1_1") (pintype "passive"))
      (node (ref "C8") (pin "1") (pinfunction "1_1") (pintype "passive"))
      (node (ref "C9") (pin "1") (pinfunction "1_1") (pintype "passive"))
      (node (ref "CLARIFIER") (pin "4") (pinfunction "P$1_4") (pintype "power_in"))
      (node (ref "CLARIFIER") (pin "5") (pinfunction "P$2_5") (pintype "power_in"))
      (node (ref "D4") (pin "A") (pinfunction "A_A") (pintype "passive"))
      (node (ref "DISPLAY1") (pin "GND@0") (pinfunction "GND_GND@0") (pintype "power_in"))
      (node (ref "DISPLAY1") (pin "GND@3") (pinfunction "GND_GND@3") (pintype "power_in"))
      (node (ref "DISPLAY1") (pin "GND@6") (pinfunction "GND_GND@6") (pintype "power_in"))
      (node (ref "DISPLAY1") (pin "GND@7") (pinfunction "GND_GND@7") (pintype "power_in"))
      (node (ref "GC-") (pin "MP") (pinfunction "MP_MP") (pintype "passive"))
      (node (ref "GND") (pin "MP") (pinfunction "MP_MP") (pintype "passive"))
      (node (ref "IC1") (pin "22") (pinfunction "GND_22") (pintype "power_in"))
      (node (ref "IC1") (pin "53") (pinfunction "GND_53") (pintype "power_in"))
      (node (ref "IC1") (pin "61") (pinfunction "PF0(ADC0)_61") (pintype "input"))
      (node (ref "IC1") (pin "63") (pinfunction "GND_63") (pintype "power_in"))
      (node (ref "IC2") (pin "4") (pinfunction "V-_4") (pintype "power_in"))
      (node (ref "IC3") (pin "10") (pinfunction "GND_10") (pintype "bidirectional"))
      (node (ref "IC3") (pin "19") (pinfunction "GND_19") (pintype "bidirectional"))
      (node (ref "IC3") (pin "2") (pinfunction "A0_2") (pintype "bidirectional"))
      (node (ref "IC3") (pin "24") (pinfunction "GND_24") (pintype "bidirectional"))
      (node (ref "IC3") (pin "3") (pinfunction "A1_3") (pintype "bidirectional"))
      (node (ref "IC3") (pin "4") (pinfunction "A2_4") (pintype "bidirectional"))
      (node (ref "IC3") (pin "5") (pinfunction "A3_5") (pintype "bidirectional"))
      (node (ref "IC4") (pin "3") (pinfunction "GND_3") (pintype "passive"))
      (node (ref "IC5") (pin "12") (pinfunction "VSS_12") (pintype "power_in"))
      (node (ref "IC5") (pin "2") (pinfunction "A1_2") (pintype "input"))
      (node (ref "IC5") (pin "3") (pinfunction "A2_3") (pintype "input"))
      (node (ref "IC6") (pin "12") (pinfunction "VSS_12") (pintype "power_in"))
      (node (ref "IC6") (pin "2") (pinfunction "A1_2") (pintype "input"))
      (node (ref "IC6") (pin "21") (pinfunction "A0_21") (pintype "input"))
      (node (ref "IC6") (pin "3") (pinfunction "A2_3") (pintype "input"))
      (node (ref "IC7") (pin "4") (pinfunction "GND_4") (pintype "power_in"))
      (node (ref "IC8") (pin "15") (pinfunction "OSC_15") (pintype "input"))
      (node (ref "IC8") (pin "16") (pinfunction "A0_16") (pintype "input"))
      (node (ref "IC8") (pin "17") (pinfunction "A1_17") (pintype "input"))
      (node (ref "IC8") (pin "18") (pinfunction "A2_18") (pintype "input"))
      (node (ref "IC8") (pin "19") (pinfunction "SA0_19") (pintype "input"))
      (node (ref "IC8") (pin "20") (pinfunction "VSS_20") (pintype "power_in"))
      (node (ref "LOCH1") (pin "B3,0") (pinfunction "MOUNT_B3,0") (pintype "passive"))
      (node (ref "LOCH2") (pin "B3,0") (pinfunction "MOUNT_B3,0") (pintype "passive"))
      (node (ref "R10") (pin "1") (pinfunction "1_1") (pintype "passive"))
      (node (ref "R20") (pin "1") (pinfunction "1_1") (pintype "passive"))
      (node (ref "R23") (pin "1") (pinfunction "1_1") (pintype "passive"))
      (node (ref "R24") (pin "3") (pinfunction "A_3") (pintype "passive"))
      (node (ref "R29") (pin "1") (pinfunction "1_1") (pintype "passive"))
      (node (ref "R3") (pin "1") (pinfunction "1_1") (pintype "passive"))
      (node (ref "R30") (pin "1") (pinfunction "1_1") (pintype "passive"))
      (node (ref "R31") (pin "2") (pinfunction "2_2") (pintype "passive"))
      (node (ref "R6") (pin "2") (pinfunction "2_2") (pintype "passive"))
      (node (ref "RF-POWER") (pin "1") (pinfunction "E_1") (pintype "passive"))
      (node (ref "RF-POWER") (pin "4") (pinfunction "P$1_4") (pintype "power_in"))
      (node (ref "RF-POWER") (pin "5") (pinfunction "P$2_5") (pintype "power_in"))
      (node (ref "SQUELCH") (pin "1") (pinfunction "E_1") (pintype "passive"))
      (node (ref "SQUELCH") (pin "4") (pinfunction "P$1_4") (pintype "power_in"))
      (node (ref "SQUELCH") (pin "5") (pinfunction "P$2_5") (pintype "power_in"))
      (node (ref "SW01") (pin "1") (pinfunction "1_1") (pintype "passive"))
      (node (ref "SW01") (pin "2") (pinfunction "2_2") (pintype "passive"))
      (node (ref "SW02") (pin "1") (pinfunction "1_1") (pintype "passive"))
      (node (ref "SW02") (pin "2") (pinfunction "2_2") (pintype "passive"))
      (node (ref "SW03") (pin "1") (pinfunction "1_1") (pintype "passive"))
      (node (ref "SW03") (pin "2") (pinfunction "2_2") (pintype "passive"))
      (node (ref "SW04") (pin "1") (pinfunction "1_1") (pintype "passive"))
      (node (ref "SW04") (pin "2") (pinfunction "2_2") (pintype "passive"))
      (node (ref "SW05") (pin "1") (pinfunction "1_1") (pintype "passive"))
      (node (ref "SW05") (pin "2") (pinfunction "2_2") (pintype "passive"))
      (node (ref "SW06") (pin "1") (pinfunction "1_1") (pintype "passive"))
      (node (ref "SW06") (pin "2") (pinfunction "2_2") (pintype "passive"))
      (node (ref "SW07") (pin "1") (pinfunction "1_1") (pintype "passive"))
      (node (ref "SW07") (pin "2") (pinfunction "2_2") (pintype "passive"))
      (node (ref "SW08") (pin "1") (pinfunction "1_1") (pintype "passive"))
      (node (ref "SW08") (pin "2") (pinfunction "2_2") (pintype "passive"))
      (node (ref "SW09") (pin "1") (pinfunction "1_1") (pintype "passive"))
      (node (ref "SW09") (pin "2") (pinfunction "2_2") (pintype "passive"))
      (node (ref "SW10") (pin "1") (pinfunction "1_1") (pintype "passive"))
      (node (ref "SW10") (pin "2") (pinfunction "2_2") (pintype "passive"))
      (node (ref "SW11") (pin "1") (pinfunction "1_1") (pintype "passive"))
      (node (ref "SW11") (pin "2") (pinfunction "2_2") (pintype "passive"))
      (node (ref "SW12") (pin "1") (pinfunction "1_1") (pintype "passive"))
      (node (ref "SW12") (pin "2") (pinfunction "2_2") (pintype "passive"))
      (node (ref "SW13") (pin "1") (pinfunction "1_1") (pintype "passive"))
      (node (ref "SW13") (pin "2") (pinfunction "2_2") (pintype "passive"))
      (node (ref "SW14") (pin "1") (pinfunction "1_1") (pintype "passive"))
      (node (ref "SW14") (pin "2") (pinfunction "2_2") (pintype "passive"))
      (node (ref "SW15") (pin "1") (pinfunction "1_1") (pintype "passive"))
      (node (ref "SW15") (pin "2") (pinfunction "2_2") (pintype "passive"))
      (node (ref "SW16") (pin "1") (pinfunction "1_1") (pintype "passive"))
      (node (ref "SW16") (pin "2") (pinfunction "2_2") (pintype "passive"))
      (node (ref "SW17") (pin "1") (pinfunction "1_1") (pintype "passive"))
      (node (ref "SW17") (pin "2") (pinfunction "2_2") (pintype "passive"))
      (node (ref "SW18") (pin "1") (pinfunction "1_1") (pintype "passive"))
      (node (ref "SW18") (pin "2") (pinfunction "2_2") (pintype "passive"))
      (node (ref "SW19") (pin "1") (pinfunction "1_1") (pintype "passive"))
      (node (ref "SW19") (pin "2") (pinfunction "2_2") (pintype "passive"))
      (node (ref "SW20") (pin "1") (pinfunction "1_1") (pintype "passive"))
      (node (ref "SW20") (pin "2") (pinfunction "2_2") (pintype "passive"))
      (node (ref "SW21") (pin "1") (pinfunction "1_1") (pintype "passive"))
      (node (ref "SW21") (pin "2") (pinfunction "2_2") (pintype "passive"))
      (node (ref "SW22") (pin "C") (pinfunction "C_C") (pintype "passive"))
      (node (ref "SW22") (pin "GND@1") (pinfunction "GND_GND@1") (pintype "power_in"))
      (node (ref "SW22") (pin "GND@2") (pinfunction "GND_GND@2") (pintype "power_in"))
      (node (ref "SW22") (pin "GND@3") (pinfunction "GND_GND@3") (pintype "power_in"))
      (node (ref "SW22") (pin "GND@4") (pinfunction "GND_GND@4") (pintype "power_in"))
      (node (ref "SW22") (pin "GND@5") (pinfunction "GND_GND@5") (pintype "power_in"))
      (node (ref "SW22") (pin "GND@6") (pinfunction "GND_GND@6") (pintype "power_in"))
      (node (ref "SW22") (pin "GND@7") (pinfunction "GND_GND@7") (pintype "power_in"))
      (node (ref "SW22") (pin "GND@8") (pinfunction "GND_GND@8") (pintype "power_in"))
      (node (ref "SWR/CAL") (pin "1") (pinfunction "E_1") (pintype "passive"))
      (node (ref "SWR/CAL") (pin "4") (pinfunction "P$1_4") (pintype "power_in"))
      (node (ref "SWR/CAL") (pin "5") (pinfunction "P$2_5") (pintype "power_in"))
      (node (ref "T1") (pin "3") (pinfunction "E_3") (pintype "passive"))
      (node (ref "T4") (pin "3") (pinfunction "E_3") (pintype "passive"))
      (node (ref "T5") (pin "C") (pinfunction "C_C") (pintype "passive"))
      (node (ref "T6") (pin "C") (pinfunction "C_C") (pintype "passive"))
      (node (ref "U1") (pin "2") (pinfunction "2_2") (pintype "passive"))
      (node (ref "U2") (pin "9") (pinfunction "9_9") (pintype "passive"))
      (node (ref "VOLUME") (pin "4") (pinfunction "P$1_4") (pintype "power_in"))
      (node (ref "VOLUME") (pin "5") (pinfunction "P$2_5") (pintype "power_in"))
    )
    (net (code "4") (name "Net-(C1-Pad1)") (class "Default")
      (node (ref "C1") (pin "1") (pinfunction "1_1") (pintype "passive"))
      (node (ref "C2") (pin "2") (pinfunction "2_2") (pintype "passive"))
      (node (ref "R28") (pin "2") (pinfunction "2_2") (pintype "passive"))
    )
    (net (code "5") (name "Net-(C1-Pad2)") (class "Default")
      (node (ref "C1") (pin "2") (pinfunction "2_2") (pintype "passive"))
      (node (ref "U1") (pin "5") (pinfunction "5_5") (pintype "passive"))
    )
    (net (code "6") (name "Net-(C4-Pad-)") (class "Default")
      (node (ref "C4") (pin "-") (pinfunction "-_-") (pintype "passive"))
      (node (ref "R15") (pin "2") (pinfunction "2_2") (pintype "passive"))
      (node (ref "R31") (pin "1") (pinfunction "1_1") (pintype "passive"))
    )
    (net (code "7") (name "Net-(C18-Pad1)") (class "Default")
      (node (ref "C18") (pin "1") (pinfunction "1_1") (pintype "passive"))
      (node (ref "PTT") (pin "MP") (pinfunction "MP_MP") (pintype "passive"))
      (node (ref "R8") (pin "2") (pinfunction "2_2") (pintype "passive"))
    )
    (net (code "8") (name "Net-(C25-Pad2)") (class "Default")
      (node (ref "C25") (pin "2") (pinfunction "2_2") (pintype "passive"))
      (node (ref "D1") (pin "A") (pinfunction "A_A") (pintype "passive"))
      (node (ref "D2") (pin "A") (pinfunction "A_A") (pintype "passive"))
      (node (ref "D3") (pin "A") (pinfunction "A_A") (pintype "passive"))
      (node (ref "U1") (pin "1") (pinfunction "1_1") (pintype "passive"))
    )
    (net (code "9") (name "Net-(C32-Pad2)") (class "Default")
      (node (ref "C32") (pin "2") (pinfunction "2_2") (pintype "passive"))
      (node (ref "R2") (pin "2") (pinfunction "2_2") (pintype "passive"))
      (node (ref "R4") (pin "2") (pinfunction "2_2") (pintype "passive"))
      (node (ref "U2") (pin "5") (pinfunction "5_5") (pintype "passive"))
    )
    (net (code "10") (name "Net-(CLARIFIER-A)") (class "Default")
      (node (ref "CLARIFIER") (pin "3") (pinfunction "A_3") (pintype "passive"))
      (node (ref "R6") (pin "1") (pinfunction "1_1") (pintype "passive"))
    )
    (net (code "11") (name "Net-(CLARIFIER-E)") (class "Default")
      (node (ref "CLARIFIER") (pin "1") (pinfunction "E_1") (pintype "passive"))
      (node (ref "R5") (pin "1") (pinfunction "1_1") (pintype "passive"))
    )
    (net (code "12") (name "Net-(CLARIFIER-S)") (class "Default")
      (node (ref "CLARIFIER") (pin "2") (pinfunction "S_2") (pintype "passive"))
      (node (ref "U2") (pin "7") (pinfunction "7_7") (pintype "passive"))
    )
    (net (code "13") (name "Net-(D4-PadC)") (class "Default")
      (node (ref "D4") (pin "C") (pinfunction "C_C") (pintype "passive"))
      (node (ref "R4") (pin "1") (pinfunction "1_1") (pintype "passive"))
      (node (ref "R5") (pin "2") (pinfunction "2_2") (pintype "passive"))
    )
    (net (code "14") (name "Net-(DISPLAY1-D1_A)") (class "Default")
      (node (ref "DISPLAY1") (pin "A1") (pinfunction "D1_A_A1") (pintype "input"))
      (node (ref "DISPLAY1") (pin "A3") (pinfunction "D3_A_A3") (pintype "input"))
      (node (ref "LED02") (pin "A") (pinfunction "A_A") (pintype "passive"))
      (node (ref "LED04") (pin "A") (pinfunction "A_A") (pintype "passive"))
      (node (ref "LED06") (pin "A") (pinfunction "A_A") (pintype "passive"))
      (node (ref "LED08") (pin "A") (pinfunction "A_A") (pintype "passive"))
      (node (ref "LED10") (pin "A") (pinfunction "A_A") (pintype "passive"))
      (node (ref "LED12") (pin "A") (pinfunction "A_A") (pintype "passive"))
      (node (ref "LED14") (pin "A") (pinfunction "A_A") (pintype "passive"))
      (node (ref "LED16") (pin "A") (pinfunction "A_A") (pintype "passive"))
      (node (ref "LED18") (pin "A") (pinfunction "A_A") (pintype "passive"))
      (node (ref "LED20") (pin "A") (pinfunction "A_A") (pintype "passive"))
      (node (ref "T3") (pin "3") (pinfunction "E_3") (pintype "passive"))
    )
    (net (code "15") (name "Net-(DISPLAY1-D1_K)") (class "Default")
      (node (ref "DISPLAY1") (pin "K1") (pinfunction "D1_K_K1") (pintype "input"))
      (node (ref "DISPLAY1") (pin "K3") (pinfunction "D3_K_K3") (pintype "input"))
      (node (ref "IC3") (pin "17") (pinfunction "/OUT10_17") (pintype "bidirectional"))
    )
    (net (code "16") (name "Net-(DISPLAY1-D2_A)") (class "Default")
      (node (ref "DISPLAY1") (pin "A2") (pinfunction "D2_A_A2") (pintype "input"))
      (node (ref "DISPLAY1") (pin "A4") (pinfunction "D4_A_A4") (pintype "input"))
      (node (ref "LED01") (pin "A") (pinfunction "A_A") (pintype "passive"))
      (node (ref "LED03") (pin "A") (pinfunction "A_A") (pintype "passive"))
      (node (ref "LED05") (pin "A") (pinfunction "A_A") (pintype "passive"))
      (node (ref "LED07") (pin "A") (pinfunction "A_A") (pintype "passive"))
      (node (ref "LED09") (pin "A") (pinfunction "A_A") (pintype "passive"))
      (node (ref "LED11") (pin "A") (pinfunction "A_A") (pintype "passive"))
      (node (ref "LED13") (pin "A") (pinfunction "A_A") (pintype "passive"))
      (node (ref "LED15") (pin "A") (pinfunction "A_A") (pintype "passive"))
      (node (ref "LED17") (pin "A") (pinfunction "A_A") (pintype "passive"))
      (node (ref "LED19") (pin "A") (pinfunction "A_A") (pintype "passive"))
      (node (ref "T2") (pin "3") (pinfunction "E_3") (pintype "passive"))
    )
    (net (code "17") (name "Net-(DISPLAY1-D2_K)") (class "Default")
      (node (ref "DISPLAY1") (pin "K2") (pinfunction "D2_K_K2") (pintype "input"))
      (node (ref "DISPLAY1") (pin "K4") (pinfunction "D4_K_K4") (pintype "input"))
      (node (ref "IC3") (pin "18") (pinfunction "/OUT11_18") (pintype "bidirectional"))
    )
    (net (code "18") (name "Net-(IC1-(A8)PC0)") (class "Default")
      (node (ref "IC1") (pin "35") (pinfunction "(A8)PC0_35") (pintype "output"))
      (node (ref "R14") (pin "2") (pinfunction "2_2") (pintype "passive"))
    )
    (net (code "19") (name "Net-(IC1-(A9)PC1)") (class "Default")
      (node (ref "IC1") (pin "36") (pinfunction "(A9)PC1_36") (pintype "output"))
      (node (ref "R16") (pin "2") (pinfunction "2_2") (pintype "passive"))
    )
    (net (code "20") (name "Net-(IC1-(A11)PC3)") (class "Default")
      (node (ref "C29") (pin "2") (pinfunction "2_2") (pintype "passive"))
      (node (ref "IC1") (pin "38") (pinfunction "(A11)PC3_38") (pintype "output"))
      (node (ref "PC3") (pin "MP") (pinfunction "MP_MP") (pintype "passive"))
    )
    (net (code "21") (name "Net-(IC1-(A12)PC4)") (class "Default")
      (node (ref "C28") (pin "2") (pinfunction "2_2") (pintype "passive"))
      (node (ref "IC1") (pin "39") (pinfunction "(A12)PC4_39") (pintype "output"))
      (node (ref "PC4") (pin "MP") (pinfunction "MP_MP") (pintype "passive"))
    )
    (net (code "22") (name "Net-(IC1-(A13)PC5)") (class "Default")
      (node (ref "C27") (pin "2") (pinfunction "2_2") (pintype "passive"))
      (node (ref "IC1") (pin "40") (pinfunction "(A13)PC5_40") (pintype "output"))
      (node (ref "PC5") (pin "MP") (pinfunction "MP_MP") (pintype "passive"))
    )
    (net (code "23") (name "Net-(IC1-(AD2)PA2)") (class "Default")
      (node (ref "C26") (pin "2") (pinfunction "2_2") (pintype "passive"))
      (node (ref "IC1") (pin "49") (pinfunction "(AD2)PA2_49") (pintype "bidirectional"))
      (node (ref "R29") (pin "2") (pinfunction "2_2") (pintype "passive"))
      (node (ref "U1") (pin "6") (pinfunction "6_6") (pintype "passive"))
    )
    (net (code "24") (name "Net-(IC1-(AD3)PA3)") (class "Default")
      (node (ref "C11") (pin "2") (pinfunction "2_2") (pintype "passive"))
      (node (ref "IC1") (pin "48") (pinfunction "(AD3)PA3_48") (pintype "bidirectional"))
      (node (ref "U1") (pin "8") (pinfunction "8_8") (pintype "passive"))
    )
    (net (code "25") (name "Net-(IC1-(AD4)PA4)") (class "Default")
      (node (ref "C12") (pin "2") (pinfunction "2_2") (pintype "passive"))
      (node (ref "IC1") (pin "47") (pinfunction "(AD4)PA4_47") (pintype "bidirectional"))
      (node (ref "U1") (pin "10") (pinfunction "10_10") (pintype "passive"))
    )
    (net (code "26") (name "Net-(IC1-(AD5)PA5)") (class "Default")
      (node (ref "C10") (pin "2") (pinfunction "2_2") (pintype "passive"))
      (node (ref "IC1") (pin "46") (pinfunction "(AD5)PA5_46") (pintype "bidirectional"))
      (node (ref "U1") (pin "9") (pinfunction "9_9") (pintype "passive"))
    )
    (net (code "27") (name "Net-(IC1-(AD6)PA6)") (class "Default")
      (node (ref "C9") (pin "2") (pinfunction "2_2") (pintype "passive"))
      (node (ref "IC1") (pin "45") (pinfunction "(AD6)PA6_45") (pintype "bidirectional"))
      (node (ref "U1") (pin "7") (pinfunction "7_7") (pintype "passive"))
    )
    (net (code "28") (name "Net-(IC1-(AD7)PA7)") (class "Default")
      (node (ref "IC1") (pin "44") (pinfunction "(AD7)PA7_44") (pintype "bidirectional"))
      (node (ref "R12") (pin "1") (pinfunction "1_1") (pintype "passive"))
    )
    (net (code "29") (name "Net-(IC1-(IC3{slash}INT7)PE7)") (class "Default")
      (node (ref "C3") (pin "+") (pinfunction "+_+") (pintype "passive"))
      (node (ref "IC1") (pin "9") (pinfunction "(IC3/INT7)PE7_9") (pintype "bidirectional"))
      (node (ref "R25") (pin "1") (pinfunction "1_1") (pintype "passive"))
    )
    (net (code "30") (name "Net-(IC1-(MISO)PB3)") (class "Default")
      (node (ref "IC1") (pin "13") (pinfunction "(MISO)PB3_13") (pintype "bidirectional"))
      (node (ref "IC7") (pin "2") (pinfunction "SO_2") (pintype "bidirectional"))
    )
    (net (code "31") (name "Net-(IC1-(MOSI)PB2)") (class "Default")
      (node (ref "IC1") (pin "12") (pinfunction "(MOSI)PB2_12") (pintype "bidirectional"))
      (node (ref "IC7") (pin "5") (pinfunction "SI_5") (pintype "input"))
    )
    (net (code "32") (name "Net-(IC1-(OC1A)PB5)") (class "Default")
      (node (ref "IC1") (pin "15") (pinfunction "(OC1A)PB5_15") (pintype "bidirectional"))
      (node (ref "R24") (pin "1") (pinfunction "E_1") (pintype "passive"))
    )
    (net (code "33") (name "Net-(IC1-(OC3A{slash}AIN1)PE3)") (class "Default")
      (node (ref "IC1") (pin "5") (pinfunction "(OC3A/AIN1)PE3_5") (pintype "bidirectional"))
      (node (ref "SPK") (pin "MP") (pinfunction "MP_MP") (pintype "passive"))
    )
    (net (code "34") (name "Net-(IC1-(OC3B{slash}INT4)PE4)") (class "Default")
      (node (ref "C31") (pin "1") (pinfunction "1_1") (pintype "passive"))
      (node (ref "D3") (pin "C") (pinfunction "C_C") (pintype "passive"))
      (node (ref "IC1") (pin "6") (pinfunction "(OC3B/INT4)PE4_6") (pintype "bidirectional"))
      (node (ref "R23") (pin "2") (pinfunction "2_2") (pintype "passive"))
    )
    (net (code "35") (name "Net-(IC1-(OC3C{slash}INT5)PE5)") (class "Default")
      (node (ref "IC1") (pin "7") (pinfunction "(OC3C/INT5)PE5_7") (pintype "bidirectional"))
      (node (ref "SW01") (pin "3") (pinfunction "3_3") (pintype "passive"))
      (node (ref "SW01") (pin "4") (pinfunction "4_4") (pintype "passive"))
    )
    (net (code "36") (name "Net-(IC1-(RXD1{slash}INT2)PD2)") (class "Default")
      (node (ref "IC1") (pin "27") (pinfunction "(RXD1/INT2)PD2_27") (pintype "bidirectional"))
      (node (ref "RX") (pin "MP") (pinfunction "MP_MP") (pintype "passive"))
    )
    (net (code "37") (name "Net-(IC1-(RXD{slash}PDI)PE0)") (class "Default")
      (node (ref "IC1") (pin "2") (pinfunction "(RXD/PDI)PE0_2") (pintype "bidirectional"))
      (node (ref "PDI") (pin "MP") (pinfunction "MP_MP") (pintype "passive"))
    )
    (net (code "38") (name "Net-(IC1-(SCK)PB1)") (class "Default")
      (node (ref "IC1") (pin "11") (pinfunction "(SCK)PB1_11") (pintype "bidirectional"))
      (node (ref "IC7") (pin "6") (pinfunction "SCK_6") (pintype "input"))
      (node (ref "SCK") (pin "MP") (pinfunction "MP_MP") (pintype "passive"))
    )
    (net (code "39") (name "Net-(IC1-(SS)PB0)") (class "Default")
      (node (ref "IC1") (pin "10") (pinfunction "(SS)PB0_10") (pintype "bidirectional"))
      (node (ref "IC7") (pin "1") (pinfunction "~{CS}_1") (pintype "input"))
    )
    (net (code "40") (name "Net-(IC1-(T3{slash}INT6)PE6)") (class "Default")
      (node (ref "C30") (pin "1") (pinfunction "1_1") (pintype "passive"))
      (node (ref "IC1") (pin "8") (pinfunction "(T3/INT6)PE6_8") (pintype "bidirectional"))
      (node (ref "PE6") (pin "MP") (pinfunction "MP_MP") (pintype "passive"))
    )
    (net (code "41") (name "Net-(IC1-(TXD1{slash}INT3)PD3)") (class "Default")
      (node (ref "IC1") (pin "28") (pinfunction "(TXD1/INT3)PD3_28") (pintype "bidirectional"))
      (node (ref "TX") (pin "MP") (pinfunction "MP_MP") (pintype "passive"))
    )
    (net (code "42") (name "Net-(IC1-(TXD{slash}PDO)PE1)") (class "Default")
      (node (ref "IC1") (pin "3") (pinfunction "(TXD/PDO)PE1_3") (pintype "bidirectional"))
      (node (ref "PDO") (pin "MP") (pinfunction "MP_MP") (pintype "passive"))
    )
    (net (code "43") (name "Net-(IC1-AVCC)") (class "Default")
      (node (ref "C7") (pin "2") (pinfunction "2_2") (pintype "passive"))
      (node (ref "IC1") (pin "64") (pinfunction "AVCC_64") (pintype "power_in"))
      (node (ref "L1") (pin "1") (pinfunction "1_1") (pintype "passive"))
    )
    (net (code "44") (name "Net-(IC1-PF1(ADC1))") (class "Default")
      (node (ref "IC1") (pin "60") (pinfunction "PF1(ADC1)_60") (pintype "input"))
      (node (ref "SWR/CAL") (pin "3") (pinfunction "A_3") (pintype "passive"))
      (node (ref "U2") (pin "10") (pinfunction "10_10") (pintype "passive"))
    )
    (net (code "45") (name "Net-(IC1-RESET)") (class "Default")
      (node (ref "IC1") (pin "20") (pinfunction "RESET_20") (pintype "input"))
      (node (ref "R32") (pin "1") (pinfunction "1_1") (pintype "passive"))
      (node (ref "RST") (pin "MP") (pinfunction "MP_MP") (pintype "passive"))
    )
    (net (code "46") (name "Net-(IC1-XTAL1)") (class "Default")
      (node (ref "C6") (pin "2") (pinfunction "2_2") (pintype "passive"))
      (node (ref "IC1") (pin "24") (pinfunction "XTAL1_24") (pintype "bidirectional"))
      (node (ref "Q1") (pin "2") (pinfunction "2_2") (pintype "passive"))
    )
    (net (code "47") (name "Net-(IC1-XTAL2)") (class "Default")
      (node (ref "C5") (pin "2") (pinfunction "2_2") (pintype "passive"))
      (node (ref "IC1") (pin "23") (pinfunction "XTAL2_23") (pintype "bidirectional"))
      (node (ref "Q1") (pin "1") (pinfunction "1_1") (pintype "passive"))
    )
    (net (code "48") (name "Net-(IC2A-+IN)") (class "Default")
      (node (ref "C20") (pin "2") (pinfunction "2_2") (pintype "passive"))
      (node (ref "IC2") (pin "3") (pinfunction "+IN_3") (pintype "input"))
      (node (ref "IC2") (pin "6") (pinfunction "-IN_6") (pintype "input"))
      (node (ref "R10") (pin "2") (pinfunction "2_2") (pintype "passive"))
      (node (ref "R17") (pin "1") (pinfunction "1_1") (pintype "passive"))
      (node (ref "UP/DOWN") (pin "MP") (pinfunction "MP_MP") (pintype "passive"))
    )
    (net (code "49") (name "Net-(IC2A--IN)") (class "Default")
      (node (ref "IC2") (pin "2") (pinfunction "-IN_2") (pintype "input"))
      (node (ref "R18") (pin "1") (pinfunction "1_1") (pintype "passive"))
      (node (ref "R19") (pin "2") (pinfunction "2_2") (pintype "passive"))
    )
    (net (code "50") (name "Net-(IC2A-OUT)") (class "Default")
      (node (ref "IC2") (pin "1") (pinfunction "OUT_1") (pintype "output"))
      (node (ref "R11") (pin "2") (pinfunction "2_2") (pintype "passive"))
      (node (ref "R21") (pin "2") (pinfunction "2_2") (pintype "passive"))
    )
    (net (code "51") (name "Net-(IC2B-+IN)") (class "Default")
      (node (ref "IC2") (pin "5") (pinfunction "+IN_5") (pintype "input"))
      (node (ref "R19") (pin "1") (pinfunction "1_1") (pintype "passive"))
      (node (ref "R20") (pin "2") (pinfunction "2_2") (pintype "passive"))
    )
    (net (code "52") (name "Net-(IC2B-OUT)") (class "Default")
      (node (ref "IC2") (pin "7") (pinfunction "OUT_7") (pintype "output"))
      (node (ref "R1") (pin "2") (pinfunction "2_2") (pintype "passive"))
      (node (ref "R22") (pin "2") (pinfunction "2_2") (pintype "passive"))
    )
    (net (code "53") (name "Net-(IC2C-V+)") (class "Default")
      (node (ref "C14") (pin "2") (pinfunction "2_2") (pintype "passive"))
      (node (ref "C19") (pin "2") (pinfunction "2_2") (pintype "passive"))
      (node (ref "IC2") (pin "8") (pinfunction "V+_8") (pintype "power_in"))
      (node (ref "IC4") (pin "1") (pinfunction "VI_1") (pintype "input"))
      (node (ref "R17") (pin "2") (pinfunction "2_2") (pintype "passive"))
      (node (ref "R18") (pin "2") (pinfunction "2_2") (pintype "passive"))
      (node (ref "U1") (pin "4") (pinfunction "4_4") (pintype "passive"))
    )
    (net (code "54") (name "Net-(IC3-REXT)") (class "Default")
      (node (ref "IC3") (pin "1") (pinfunction "REXT_1") (pintype "bidirectional"))
      (node (ref "R3") (pin "2") (pinfunction "2_2") (pintype "passive"))
    )
    (net (code "55") (name "Net-(IC3-{slash}OUT0)") (class "Default")
      (node (ref "IC3") (pin "6") (pinfunction "/OUT0_6") (pintype "bidirectional"))
      (node (ref "LED05") (pin "C") (pinfunction "C_C") (pintype "passive"))
      (node (ref "LED06") (pin "C") (pinfunction "C_C") (pintype "passive"))
    )
    (net (code "56") (name "Net-(IC3-{slash}OUT1)") (class "Default")
      (node (ref "IC3") (pin "7") (pinfunction "/OUT1_7") (pintype "bidirectional"))
      (node (ref "LED07") (pin "C") (pinfunction "C_C") (pintype "passive"))
      (node (ref "LED08") (pin "C") (pinfunction "C_C") (pintype "passive"))
    )
    (net (code "57") (name "Net-(IC3-{slash}OUT2)") (class "Default")
      (node (ref "IC3") (pin "8") (pinfunction "/OUT2_8") (pintype "bidirectional"))
      (node (ref "LED09") (pin "C") (pinfunction "C_C") (pintype "passive"))
      (node (ref "LED10") (pin "C") (pinfunction "C_C") (pintype "passive"))
    )
    (net (code "58") (name "Net-(IC3-{slash}OUT3)") (class "Default")
      (node (ref "IC3") (pin "9") (pinfunction "/OUT3_9") (pintype "bidirectional"))
      (node (ref "LED11") (pin "C") (pinfunction "C_C") (pintype "passive"))
      (node (ref "LED12") (pin "C") (pinfunction "C_C") (pintype "passive"))
    )
    (net (code "59") (name "Net-(IC3-{slash}OUT4)") (class "Default")
      (node (ref "IC3") (pin "11") (pinfunction "/OUT4_11") (pintype "bidirectional"))
      (node (ref "LED13") (pin "C") (pinfunction "C_C") (pintype "passive"))
      (node (ref "LED14") (pin "C") (pinfunction "C_C") (pintype "passive"))
    )
    (net (code "60") (name "Net-(IC3-{slash}OUT5)") (class "Default")
      (node (ref "IC3") (pin "12") (pinfunction "/OUT5_12") (pintype "bidirectional"))
      (node (ref "LED15") (pin "C") (pinfunction "C_C") (pintype "passive"))
      (node (ref "LED16") (pin "C") (pinfunction "C_C") (pintype "passive"))
    )
    (net (code "61") (name "Net-(IC3-{slash}OUT6)") (class "Default")
      (node (ref "IC3") (pin "13") (pinfunction "/OUT6_13") (pintype "bidirectional"))
      (node (ref "LED19") (pin "C") (pinfunction "C_C") (pintype "passive"))
      (node (ref "LED20") (pin "C") (pinfunction "C_C") (pintype "passive"))
    )
    (net (code "62") (name "Net-(IC3-{slash}OUT7)") (class "Default")
      (node (ref "IC3") (pin "14") (pinfunction "/OUT7_14") (pintype "bidirectional"))
      (node (ref "LED17") (pin "C") (pinfunction "C_C") (pintype "passive"))
      (node (ref "LED18") (pin "C") (pinfunction "C_C") (pintype "passive"))
    )
    (net (code "63") (name "Net-(IC3-{slash}OUT8)") (class "Default")
      (node (ref "IC3") (pin "15") (pinfunction "/OUT8_15") (pintype "bidirectional"))
      (node (ref "LED03") (pin "C") (pinfunction "C_C") (pintype "passive"))
      (node (ref "LED04") (pin "C") (pinfunction "C_C") (pintype "passive"))
    )
    (net (code "64") (name "Net-(IC3-{slash}OUT9)") (class "Default")
      (node (ref "IC3") (pin "16") (pinfunction "/OUT9_16") (pintype "bidirectional"))
      (node (ref "LED01") (pin "C") (pinfunction "C_C") (pintype "passive"))
      (node (ref "LED02") (pin "C") (pinfunction "C_C") (pintype "passive"))
    )
    (net (code "65") (name "Net-(IC3-{slash}RESET)") (class "Default")
      (node (ref "IC3") (pin "25") (pinfunction "/RESET_25") (pintype "bidirectional"))
      (node (ref "R13") (pin "2") (pinfunction "2_2") (pintype "passive"))
    )
    (net (code "66") (name "Net-(IC4-VO)") (class "Default")
      (node (ref "C15") (pin "2") (pinfunction "2_2") (pintype "passive"))
      (node (ref "IC4") (pin "2") (pinfunction "VO_2") (pintype "passive"))
      (node (ref "T2") (pin "4") (pinfunction "C_4") (pintype "passive"))
      (node (ref "T3") (pin "4") (pinfunction "C_4") (pintype "passive"))
    )
    (net (code "67") (name "Net-(IC5-I{slash}O0.0)") (class "Default")
      (node (ref "IC5") (pin "4") (pinfunction "I/O0.0_4") (pintype "bidirectional"))
      (node (ref "SW13") (pin "3") (pinfunction "3_3") (pintype "passive"))
      (node (ref "SW13") (pin "4") (pinfunction "4_4") (pintype "passive"))
    )
    (net (code "68") (name "Net-(IC5-I{slash}O0.1)") (class "Default")
      (node (ref "IC5") (pin "5") (pinfunction "I/O0.1_5") (pintype "bidirectional"))
      (node (ref "SW14") (pin "3") (pinfunction "3_3") (pintype "passive"))
      (node (ref "SW14") (pin "4") (pinfunction "4_4") (pintype "passive"))
    )
    (net (code "69") (name "Net-(IC5-I{slash}O0.2)") (class "Default")
      (node (ref "IC5") (pin "6") (pinfunction "I/O0.2_6") (pintype "bidirectional"))
      (node (ref "SW15") (pin "3") (pinfunction "3_3") (pintype "passive"))
      (node (ref "SW15") (pin "4") (pinfunction "4_4") (pintype "passive"))
    )
    (net (code "70") (name "Net-(IC5-I{slash}O0.6)") (class "Default")
      (node (ref "IC5") (pin "10") (pinfunction "I/O0.6_10") (pintype "bidirectional"))
      (node (ref "T5") (pin "E") (pinfunction "E_E") (pintype "passive"))
    )
    (net (code "71") (name "Net-(IC5-I{slash}O0.7)") (class "Default")
      (node (ref "IC5") (pin "11") (pinfunction "I/O0.7_11") (pintype "bidirectional"))
      (node (ref "T6") (pin "E") (pinfunction "E_E") (pintype "passive"))
    )
    (net (code "72") (name "Net-(IC5-I{slash}O1.0)") (class "Default")
      (node (ref "IC5") (pin "13") (pinfunction "I/O1.0_13") (pintype "bidirectional"))
      (node (ref "SW20") (pin "3") (pinfunction "3_3") (pintype "passive"))
      (node (ref "SW20") (pin "4") (pinfunction "4_4") (pintype "passive"))
    )
    (net (code "73") (name "Net-(IC5-I{slash}O1.1)") (class "Default")
      (node (ref "C21") (pin "2") (pinfunction "2_2") (pintype "passive"))
      (node (ref "IC5") (pin "14") (pinfunction "I/O1.1_14") (pintype "bidirectional"))
      (node (ref "SW22") (pin "B") (pinfunction "B_B") (pintype "passive"))
    )
    (net (code "74") (name "Net-(IC5-I{slash}O1.2)") (class "Default")
      (node (ref "C22") (pin "2") (pinfunction "2_2") (pintype "passive"))
      (node (ref "IC5") (pin "15") (pinfunction "I/O1.2_15") (pintype "bidirectional"))
      (node (ref "SW22") (pin "A") (pinfunction "A_A") (pintype "passive"))
    )
    (net (code "75") (name "Net-(IC5-I{slash}O1.3)") (class "Default")
      (node (ref "IC5") (pin "16") (pinfunction "I/O1.3_16") (pintype "bidirectional"))
      (node (ref "SW21") (pin "3") (pinfunction "3_3") (pintype "passive"))
      (node (ref "SW21") (pin "4") (pinfunction "4_4") (pintype "passive"))
    )
    (net (code "76") (name "Net-(IC5-I{slash}O1.4)") (class "Default")
      (node (ref "IC5") (pin "17") (pinfunction "I/O1.4_17") (pintype "bidirectional"))
      (node (ref "SW18") (pin "3") (pinfunction "3_3") (pintype "passive"))
      (node (ref "SW18") (pin "4") (pinfunction "4_4") (pintype "passive"))
    )
    (net (code "77") (name "Net-(IC5-I{slash}O1.5)") (class "Default")
      (node (ref "IC5") (pin "18") (pinfunction "I/O1.5_18") (pintype "bidirectional"))
      (node (ref "SW19") (pin "3") (pinfunction "3_3") (pintype "passive"))
      (node (ref "SW19") (pin "4") (pinfunction "4_4") (pintype "passive"))
    )
    (net (code "78") (name "Net-(IC5-I{slash}O1.6)") (class "Default")
      (node (ref "IC5") (pin "19") (pinfunction "I/O1.6_19") (pintype "bidirectional"))
      (node (ref "SW16") (pin "3") (pinfunction "3_3") (pintype "passive"))
      (node (ref "SW16") (pin "4") (pinfunction "4_4") (pintype "passive"))
    )
    (net (code "79") (name "Net-(IC5-I{slash}O1.7)") (class "Default")
      (node (ref "IC5") (pin "20") (pinfunction "I/O1.7_20") (pintype "bidirectional"))
      (node (ref "SW17") (pin "3") (pinfunction "3_3") (pintype "passive"))
      (node (ref "SW17") (pin "4") (pinfunction "4_4") (pintype "passive"))
    )
    (net (code "80") (name "Net-(IC5-~{INT})") (class "Default")
      (node (ref "IC5") (pin "1") (pinfunction "~{INT}_1") (pintype "output"))
      (node (ref "IC6") (pin "1") (pinfunction "~{INT}_1") (pintype "output"))
      (node (ref "R25") (pin "2") (pinfunction "2_2") (pintype "passive"))
    )
    (net (code "81") (name "Net-(IC6-I{slash}O0.0)") (class "Default")
      (node (ref "IC6") (pin "4") (pinfunction "I/O0.0_4") (pintype "bidirectional"))
      (node (ref "SW08") (pin "3") (pinfunction "3_3") (pintype "passive"))
      (node (ref "SW08") (pin "4") (pinfunction "4_4") (pintype "passive"))
    )
    (net (code "82") (name "Net-(IC6-I{slash}O0.1)") (class "Default")
      (node (ref "IC6") (pin "5") (pinfunction "I/O0.1_5") (pintype "bidirectional"))
      (node (ref "SW07") (pin "3") (pinfunction "3_3") (pintype "passive"))
      (node (ref "SW07") (pin "4") (pinfunction "4_4") (pintype "passive"))
    )
    (net (code "83") (name "Net-(IC6-I{slash}O0.2)") (class "Default")
      (node (ref "IC6") (pin "6") (pinfunction "I/O0.2_6") (pintype "bidirectional"))
      (node (ref "SW06") (pin "3") (pinfunction "3_3") (pintype "passive"))
      (node (ref "SW06") (pin "4") (pinfunction "4_4") (pintype "passive"))
    )
    (net (code "84") (name "Net-(IC6-I{slash}O0.3)") (class "Default")
      (node (ref "IC6") (pin "7") (pinfunction "I/O0.3_7") (pintype "bidirectional"))
      (node (ref "SW05") (pin "3") (pinfunction "3_3") (pintype "passive"))
      (node (ref "SW05") (pin "4") (pinfunction "4_4") (pintype "passive"))
    )
    (net (code "85") (name "Net-(IC6-I{slash}O0.4)") (class "Default")
      (node (ref "IC6") (pin "8") (pinfunction "I/O0.4_8") (pintype "bidirectional"))
      (node (ref "SW04") (pin "3") (pinfunction "3_3") (pintype "passive"))
      (node (ref "SW04") (pin "4") (pinfunction "4_4") (pintype "passive"))
    )
    (net (code "86") (name "Net-(IC6-I{slash}O0.5)") (class "Default")
      (node (ref "IC6") (pin "9") (pinfunction "I/O0.5_9") (pintype "bidirectional"))
      (node (ref "SW03") (pin "3") (pinfunction "3_3") (pintype "passive"))
      (node (ref "SW03") (pin "4") (pinfunction "4_4") (pintype "passive"))
    )
    (net (code "87") (name "Net-(IC6-I{slash}O0.6)") (class "Default")
      (node (ref "IC6") (pin "10") (pinfunction "I/O0.6_10") (pintype "bidirectional"))
      (node (ref "SW02") (pin "3") (pinfunction "3_3") (pintype "passive"))
      (node (ref "SW02") (pin "4") (pinfunction "4_4") (pintype "passive"))
    )
    (net (code "88") (name "Net-(IC6-I{slash}O1.0)") (class "Default")
      (node (ref "IC6") (pin "13") (pinfunction "I/O1.0_13") (pintype "bidirectional"))
      (node (ref "SW09") (pin "3") (pinfunction "3_3") (pintype "passive"))
      (node (ref "SW09") (pin "4") (pinfunction "4_4") (pintype "passive"))
    )
    (net (code "89") (name "Net-(IC6-I{slash}O1.1)") (class "Default")
      (node (ref "IC6") (pin "14") (pinfunction "I/O1.1_14") (pintype "bidirectional"))
      (node (ref "R8") (pin "1") (pinfunction "1_1") (pintype "passive"))
      (node (ref "R9") (pin "2") (pinfunction "2_2") (pintype "passive"))
    )
    (net (code "90") (name "Net-(IC6-I{slash}O1.2)") (class "Default")
      (node (ref "IC6") (pin "15") (pinfunction "I/O1.2_15") (pintype "bidirectional"))
      (node (ref "SW10") (pin "3") (pinfunction "3_3") (pintype "passive"))
      (node (ref "SW10") (pin "4") (pinfunction "4_4") (pintype "passive"))
    )
    (net (code "91") (name "Net-(IC6-I{slash}O1.3)") (class "Default")
      (node (ref "IC6") (pin "16") (pinfunction "I/O1.3_16") (pintype "bidirectional"))
      (node (ref "SW11") (pin "3") (pinfunction "3_3") (pintype "passive"))
      (node (ref "SW11") (pin "4") (pinfunction "4_4") (pintype "passive"))
    )
    (net (code "92") (name "Net-(IC6-I{slash}O1.4)") (class "Default")
      (node (ref "IC6") (pin "17") (pinfunction "I/O1.4_17") (pintype "bidirectional"))
      (node (ref "SW12") (pin "3") (pinfunction "3_3") (pintype "passive"))
      (node (ref "SW12") (pin "4") (pinfunction "4_4") (pintype "passive"))
    )
    (net (code "93") (name "Net-(IC8-BP0)") (class "Default")
      (node (ref "DISPLAY1") (pin "COM1") (pinfunction "COM1_COM1") (pintype "input"))
      (node (ref "IC8") (pin "25") (pinfunction "BP0_25") (pintype "output"))
    )
    (net (code "94") (name "Net-(IC8-BP1)") (class "Default")
      (node (ref "DISPLAY1") (pin "COM2") (pinfunction "COM2_COM2") (pintype "input"))
      (node (ref "IC8") (pin "26") (pinfunction "BP1_26") (pintype "output"))
    )
    (net (code "95") (name "Net-(IC8-BP2)") (class "Default")
      (node (ref "DISPLAY1") (pin "COM3") (pinfunction "COM3_COM3") (pintype "input"))
      (node (ref "IC8") (pin "27") (pinfunction "BP2_27") (pintype "output"))
    )
    (net (code "96") (name "Net-(IC8-S0)") (class "Default")
      (node (ref "DISPLAY1") (pin "SEG01") (pinfunction "SEG01_SEG01") (pintype "input"))
      (node (ref "IC8") (pin "29") (pinfunction "S0_29") (pintype "output"))
    )
    (net (code "97") (name "Net-(IC8-S1)") (class "Default")
      (node (ref "DISPLAY1") (pin "SEG02") (pinfunction "SEG02_SEG02") (pintype "input"))
      (node (ref "IC8") (pin "30") (pinfunction "S1_30") (pintype "output"))
    )
    (net (code "98") (name "Net-(IC8-S2)") (class "Default")
      (node (ref "DISPLAY1") (pin "SEG03") (pinfunction "SEG03_SEG03") (pintype "input"))
      (node (ref "IC8") (pin "31") (pinfunction "S2_31") (pintype "output"))
    )
    (net (code "99") (name "Net-(IC8-S3)") (class "Default")
      (node (ref "DISPLAY1") (pin "SEG04") (pinfunction "SEG04_SEG04") (pintype "input"))
      (node (ref "IC8") (pin "32") (pinfunction "S3_32") (pintype "output"))
    )
    (net (code "100") (name "Net-(IC8-S4)") (class "Default")
      (node (ref "DISPLAY1") (pin "SEG05") (pinfunction "SEG05_SEG05") (pintype "input"))
      (node (ref "IC8") (pin "34") (pinfunction "S4_34") (pintype "output"))
    )
    (net (code "101") (name "Net-(IC8-S5)") (class "Default")
      (node (ref "DISPLAY1") (pin "SEG06") (pinfunction "SEG06_SEG06") (pintype "input"))
      (node (ref "IC8") (pin "35") (pinfunction "S5_35") (pintype "output"))
    )
    (net (code "102") (name "Net-(IC8-S6)") (class "Default")
      (node (ref "DISPLAY1") (pin "SEG07") (pinfunction "SEG07_SEG07") (pintype "input"))
      (node (ref "IC8") (pin "36") (pinfunction "S6_36") (pintype "output"))
    )
    (net (code "103") (name "Net-(IC8-S7)") (class "Default")
      (node (ref "DISPLAY1") (pin "SEG08") (pinfunction "SEG08_SEG08") (pintype "input"))
      (node (ref "IC8") (pin "37") (pinfunction "S7_37") (pintype "output"))
    )
    (net (code "104") (name "Net-(IC8-S8)") (class "Default")
      (node (ref "DISPLAY1") (pin "SEG09") (pinfunction "SEG09_SEG09") (pintype "input"))
      (node (ref "IC8") (pin "38") (pinfunction "S8_38") (pintype "output"))
    )
    (net (code "105") (name "Net-(IC8-S9)") (class "Default")
      (node (ref "DISPLAY1") (pin "SEG10") (pinfunction "SEG10_SEG10") (pintype "input"))
      (node (ref "IC8") (pin "39") (pinfunction "S9_39") (pintype "output"))
    )
    (net (code "106") (name "Net-(IC8-S10)") (class "Default")
      (node (ref "DISPLAY1") (pin "SEG11") (pinfunction "SEG11_SEG11") (pintype "input"))
      (node (ref "IC8") (pin "40") (pinfunction "S10_40") (pintype "output"))
    )
    (net (code "107") (name "Net-(IC8-S11)") (class "Default")
      (node (ref "DISPLAY1") (pin "SEG12") (pinfunction "SEG12_SEG12") (pintype "input"))
      (node (ref "IC8") (pin "41") (pinfunction "S11_41") (pintype "output"))
    )
    (net (code "108") (name "Net-(IC8-S12)") (class "Default")
      (node (ref "DISPLAY1") (pin "SEG13") (pinfunction "SEG13_SEG13") (pintype "input"))
      (node (ref "IC8") (pin "42") (pinfunction "S12_42") (pintype "output"))
    )
    (net (code "109") (name "Net-(IC8-S13)") (class "Default")
      (node (ref "DISPLAY1") (pin "SEG14") (pinfunction "SEG14_SEG14") (pintype "input"))
      (node (ref "IC8") (pin "43") (pinfunction "S13_43") (pintype "output"))
    )
    (net (code "110") (name "Net-(IC8-S14)") (class "Default")
      (node (ref "DISPLAY1") (pin "SEG15") (pinfunction "SEG15_SEG15") (pintype "input"))
      (node (ref "IC8") (pin "44") (pinfunction "S14_44") (pintype "output"))
    )
    (net (code "111") (name "Net-(IC8-S15)") (class "Default")
      (node (ref "DISPLAY1") (pin "SEG16") (pinfunction "SEG16_SEG16") (pintype "input"))
      (node (ref "IC8") (pin "45") (pinfunction "S15_45") (pintype "output"))
    )
    (net (code "112") (name "Net-(IC8-S16)") (class "Default")
      (node (ref "DISPLAY1") (pin "SEG17") (pinfunction "SEG17_SEG17") (pintype "input"))
      (node (ref "IC8") (pin "46") (pinfunction "S16_46") (pintype "output"))
    )
    (net (code "113") (name "Net-(IC8-S17)") (class "Default")
      (node (ref "DISPLAY1") (pin "SEG18") (pinfunction "SEG18_SEG18") (pintype "input"))
      (node (ref "IC8") (pin "47") (pinfunction "S17_47") (pintype "output"))
    )
    (net (code "114") (name "Net-(IC8-S18)") (class "Default")
      (node (ref "DISPLAY1") (pin "SEG19") (pinfunction "SEG19_SEG19") (pintype "input"))
      (node (ref "IC8") (pin "49") (pinfunction "S18_49") (pintype "output"))
    )
    (net (code "115") (name "Net-(IC8-S19)") (class "Default")
      (node (ref "DISPLAY1") (pin "SEG20") (pinfunction "SEG20_SEG20") (pintype "input"))
      (node (ref "IC8") (pin "50") (pinfunction "S19_50") (pintype "output"))
    )
    (net (code "116") (name "Net-(IC8-S20)") (class "Default")
      (node (ref "DISPLAY1") (pin "SEG21") (pinfunction "SEG21_SEG21") (pintype "input"))
      (node (ref "IC8") (pin "51") (pinfunction "S20_51") (pintype "output"))
    )
    (net (code "117") (name "Net-(IC8-S21)") (class "Default")
      (node (ref "DISPLAY1") (pin "SEG22") (pinfunction "SEG22_SEG22") (pintype "input"))
      (node (ref "IC8") (pin "52") (pinfunction "S21_52") (pintype "output"))
    )
    (net (code "118") (name "Net-(IC8-S22)") (class "Default")
      (node (ref "DISPLAY1") (pin "SEG23") (pinfunction "SEG23_SEG23") (pintype "input"))
      (node (ref "IC8") (pin "53") (pinfunction "S22_53") (pintype "output"))
    )
    (net (code "119") (name "Net-(IC8-S23)") (class "Default")
      (node (ref "DISPLAY1") (pin "SEG24") (pinfunction "SEG24_SEG24") (pintype "input"))
      (node (ref "IC8") (pin "54") (pinfunction "S23_54") (pintype "output"))
    )
    (net (code "120") (name "Net-(IC8-S24)") (class "Default")
      (node (ref "DISPLAY1") (pin "SEG25") (pinfunction "SEG25_SEG25") (pintype "input"))
      (node (ref "IC8") (pin "55") (pinfunction "S24_55") (pintype "output"))
    )
    (net (code "121") (name "Net-(IC8-S25)") (class "Default")
      (node (ref "DISPLAY1") (pin "SEG26") (pinfunction "SEG26_SEG26") (pintype "input"))
      (node (ref "IC8") (pin "56") (pinfunction "S25_56") (pintype "output"))
    )
    (net (code "122") (name "Net-(IC8-S26)") (class "Default")
      (node (ref "DISPLAY1") (pin "SEG27") (pinfunction "SEG27_SEG27") (pintype "input"))
      (node (ref "IC8") (pin "57") (pinfunction "S26_57") (pintype "output"))
    )
    (net (code "123") (name "Net-(IC8-S27)") (class "Default")
      (node (ref "DISPLAY1") (pin "SEG28") (pinfunction "SEG28_SEG28") (pintype "input"))
      (node (ref "IC8") (pin "58") (pinfunction "S27_58") (pintype "output"))
    )
    (net (code "124") (name "Net-(IC8-S28)") (class "Default")
      (node (ref "DISPLAY1") (pin "SEG29") (pinfunction "SEG29_SEG29") (pintype "input"))
      (node (ref "IC8") (pin "59") (pinfunction "S28_59") (pintype "output"))
    )
    (net (code "125") (name "Net-(IC8-S29)") (class "Default")
      (node (ref "DISPLAY1") (pin "SEG30") (pinfunction "SEG30_SEG30") (pintype "input"))
      (node (ref "IC8") (pin "60") (pinfunction "S29_60") (pintype "output"))
    )
    (net (code "126") (name "Net-(IC8-S30)") (class "Default")
      (node (ref "DISPLAY1") (pin "SEG31") (pinfunction "SEG31_SEG31") (pintype "input"))
      (node (ref "IC8") (pin "61") (pinfunction "S30_61") (pintype "output"))
    )
    (net (code "127") (name "Net-(IC8-S31)") (class "Default")
      (node (ref "DISPLAY1") (pin "SEG32") (pinfunction "SEG32_SEG32") (pintype "input"))
      (node (ref "IC8") (pin "62") (pinfunction "S31_62") (pintype "output"))
    )
    (net (code "128") (name "Net-(IC8-S32)") (class "Default")
      (node (ref "DISPLAY1") (pin "SEG33") (pinfunction "SEG33_SEG33") (pintype "input"))
      (node (ref "IC8") (pin "63") (pinfunction "S32_63") (pintype "output"))
    )
    (net (code "129") (name "Net-(IC8-VLCD)") (class "Default")
      (node (ref "IC8") (pin "21") (pinfunction "VLCD_21") (pintype "power_in"))
      (node (ref "R30") (pin "2") (pinfunction "2_2") (pintype "passive"))
    )
    (net (code "130") (name "Net-(R1-Pad1)") (class "Default")
      (node (ref "R1") (pin "1") (pinfunction "1_1") (pintype "passive"))
      (node (ref "T6") (pin "B") (pinfunction "B_B") (pintype "passive"))
    )
    (net (code "131") (name "Net-(R7-Pad2)") (class "Default")
      (node (ref "R7") (pin "2") (pinfunction "2_2") (pintype "passive"))
      (node (ref "U2") (pin "8") (pinfunction "8_8") (pintype "passive"))
    )
    (net (code "132") (name "Net-(R11-Pad1)") (class "Default")
      (node (ref "R11") (pin "1") (pinfunction "1_1") (pintype "passive"))
      (node (ref "T5") (pin "B") (pinfunction "B_B") (pintype "passive"))
    )
    (net (code "133") (name "Net-(R24-S)") (class "Default")
      (node (ref "R24") (pin "2") (pinfunction "S_2") (pintype "passive"))
      (node (ref "R28") (pin "1") (pinfunction "1_1") (pintype "passive"))
    )
    (net (code "134") (name "Net-(RF-POWER-S)") (class "Default")
      (node (ref "RF-POWER") (pin "2") (pinfunction "S_2") (pintype "passive"))
      (node (ref "U2") (pin "6") (pinfunction "6_6") (pintype "passive"))
    )
    (net (code "135") (name "Net-(SQUELCH-A)") (class "Default")
      (node (ref "R2") (pin "1") (pinfunction "1_1") (pintype "passive"))
      (node (ref "SQUELCH") (pin "3") (pinfunction "A_3") (pintype "passive"))
    )
    (net (code "136") (name "Net-(SQUELCH-S)") (class "Default")
      (node (ref "SQUELCH") (pin "2") (pinfunction "S_2") (pintype "passive"))
      (node (ref "U2") (pin "4") (pinfunction "4_4") (pintype "passive"))
    )
    (net (code "137") (name "Net-(SWR/CAL-S)") (class "Default")
      (node (ref "R7") (pin "1") (pinfunction "1_1") (pintype "passive"))
      (node (ref "SWR/CAL") (pin "2") (pinfunction "S_2") (pintype "passive"))
    )
    (net (code "138") (name "Net-(T1-B)") (class "Default")
      (node (ref "R12") (pin "2") (pinfunction "2_2") (pintype "passive"))
      (node (ref "T1") (pin "1") (pinfunction "B_1") (pintype "passive"))
    )
    (net (code "139") (name "Net-(T1-C)") (class "Default")
      (node (ref "T1") (pin "4") (pinfunction "C_4") (pintype "passive"))
      (node (ref "U1") (pin "3") (pinfunction "3_3") (pintype "passive"))
    )
    (net (code "140") (name "Net-(T2-B)") (class "Default")
      (node (ref "R14") (pin "1") (pinfunction "1_1") (pintype "passive"))
      (node (ref "T2") (pin "1") (pinfunction "B_1") (pintype "passive"))
    )
    (net (code "141") (name "Net-(T3-B)") (class "Default")
      (node (ref "R16") (pin "1") (pinfunction "1_1") (pintype "passive"))
      (node (ref "T3") (pin "1") (pinfunction "B_1") (pintype "passive"))
    )
    (net (code "142") (name "Net-(T4-B)") (class "Default")
      (node (ref "R15") (pin "1") (pinfunction "1_1") (pintype "passive"))
      (node (ref "T4") (pin "1") (pinfunction "B_1") (pintype "passive"))
    )
    (net (code "143") (name "Net-(T4-C)") (class "Default")
      (node (ref "R32") (pin "2") (pinfunction "2_2") (pintype "passive"))
      (node (ref "T4") (pin "4") (pinfunction "C_4") (pintype "passive"))
    )
    (net (code "144") (name "Net-(VOLUME-A)") (class "Default")
      (node (ref "U2") (pin "3") (pinfunction "3_3") (pintype "passive"))
      (node (ref "VOLUME") (pin "3") (pinfunction "A_3") (pintype "passive"))
    )
    (net (code "145") (name "Net-(VOLUME-E)") (class "Default")
      (node (ref "U2") (pin "2") (pinfunction "2_2") (pintype "passive"))
      (node (ref "VOLUME") (pin "1") (pinfunction "E_1") (pintype "passive"))
    )
    (net (code "146") (name "Net-(VOLUME-S)") (class "Default")
      (node (ref "U2") (pin "1") (pinfunction "1_1") (pintype "passive"))
      (node (ref "VOLUME") (pin "2") (pinfunction "S_2") (pintype "passive"))
    )
    (net (code "147") (name "VCC") (class "Default")
      (node (ref "5V") (pin "MP") (pinfunction "MP_MP") (pintype "passive"))
      (node (ref "C13") (pin "2") (pinfunction "2_2") (pintype "passive"))
      (node (ref "C17") (pin "2") (pinfunction "2_2") (pintype "passive"))
      (node (ref "C23") (pin "2") (pinfunction "2_2") (pintype "passive"))
      (node (ref "C24") (pin "2") (pinfunction "2_2") (pintype "passive"))
      (node (ref "C4") (pin "+") (pinfunction "+_+") (pintype "passive"))
      (node (ref "D2") (pin "C") (pinfunction "C_C") (pintype "passive"))
      (node (ref "IC3") (pin "28") (pinfunction "VCC_28") (pintype "bidirectional"))
      (node (ref "IC5") (pin "21") (pinfunction "A0_21") (pintype "input"))
      (node (ref "IC5") (pin "24") (pinfunction "VDD_24") (pintype "power_in"))
      (node (ref "IC6") (pin "24") (pinfunction "VDD_24") (pintype "power_in"))
      (node (ref "IC8") (pin "14") (pinfunction "VDD_14") (pintype "power_in"))
      (node (ref "R13") (pin "1") (pinfunction "1_1") (pintype "passive"))
      (node (ref "R21") (pin "1") (pinfunction "1_1") (pintype "passive"))
      (node (ref "R22") (pin "1") (pinfunction "1_1") (pintype "passive"))
      (node (ref "R26") (pin "2") (pinfunction "2_2") (pintype "passive"))
      (node (ref "R27") (pin "2") (pinfunction "2_2") (pintype "passive"))
      (node (ref "R9") (pin "1") (pinfunction "1_1") (pintype "passive"))
    )
    (net (code "148") (name "VCCMEM") (class "Default")
      (node (ref "C16") (pin "2") (pinfunction "2_2") (pintype "passive"))
      (node (ref "C8") (pin "2") (pinfunction "2_2") (pintype "passive"))
      (node (ref "D1") (pin "C") (pinfunction "C_C") (pintype "passive"))
      (node (ref "GC+") (pin "MP") (pinfunction "MP_MP") (pintype "passive"))
      (node (ref "IC1") (pin "21") (pinfunction "VCC_21") (pintype "power_in"))
      (node (ref "IC1") (pin "52") (pinfunction "VCC_52") (pintype "power_in"))
      (node (ref "IC7") (pin "3") (pinfunction "~{WP}_3") (pintype "input"))
      (node (ref "IC7") (pin "7") (pinfunction "~{HOLD}_7") (pintype "input"))
      (node (ref "IC7") (pin "8") (pinfunction "VCC_8") (pintype "power_in"))
      (node (ref "L1") (pin "2") (pinfunction "2_2") (pintype "passive"))
    )
    (net (code "149") (name "unconnected-(IC1-(A10)PC2-Pad37)") (class "Default")
      (node (ref "IC1") (pin "37") (pinfunction "(A10)PC2_37") (pintype "output"))
    )
    (net (code "150") (name "unconnected-(IC1-(A14)PC6-Pad41)") (class "Default")
      (node (ref "IC1") (pin "41") (pinfunction "(A14)PC6_41") (pintype "output"))
    )
    (net (code "151") (name "unconnected-(IC1-(A15)PC7-Pad42)") (class "Default")
      (node (ref "IC1") (pin "42") (pinfunction "(A15)PC7_42") (pintype "output"))
    )
    (net (code "152") (name "unconnected-(IC1-(AD0)PA0-Pad51)") (class "Default")
      (node (ref "IC1") (pin "51") (pinfunction "(AD0)PA0_51") (pintype "bidirectional"))
    )
    (net (code "153") (name "unconnected-(IC1-(AD1)PA1-Pad50)") (class "Default")
      (node (ref "IC1") (pin "50") (pinfunction "(AD1)PA1_50") (pintype "bidirectional"))
    )
    (net (code "154") (name "unconnected-(IC1-(IC1)PD4-Pad29)") (class "Default")
      (node (ref "IC1") (pin "29") (pinfunction "(IC1)PD4_29") (pintype "bidirectional"))
    )
    (net (code "155") (name "unconnected-(IC1-(OC0)PB4-Pad14)") (class "Default")
      (node (ref "IC1") (pin "14") (pinfunction "(OC0)PB4_14") (pintype "bidirectional"))
    )
    (net (code "156") (name "unconnected-(IC1-(OC1B)PB6-Pad16)") (class "Default")
      (node (ref "IC1") (pin "16") (pinfunction "(OC1B)PB6_16") (pintype "bidirectional"))
    )
    (net (code "157") (name "unconnected-(IC1-(OC2{slash}OC1C)PB7-Pad17)") (class "Default")
      (node (ref "IC1") (pin "17") (pinfunction "(OC2/OC1C)PB7_17") (pintype "bidirectional"))
    )
    (net (code "158") (name "unconnected-(IC1-(T1)PD6-Pad31)") (class "Default")
      (node (ref "IC1") (pin "31") (pinfunction "(T1)PD6_31") (pintype "bidirectional"))
    )
    (net (code "159") (name "unconnected-(IC1-(T2)PD7-Pad32)") (class "Default")
      (node (ref "IC1") (pin "32") (pinfunction "(T2)PD7_32") (pintype "bidirectional"))
    )
    (net (code "160") (name "unconnected-(IC1-(XCK0{slash}AIN0)PE2-Pad4)") (class "Default")
      (node (ref "IC1") (pin "4") (pinfunction "(XCK0/AIN0)PE2_4") (pintype "bidirectional"))
    )
    (net (code "161") (name "unconnected-(IC1-(XCK1)PD5-Pad30)") (class "Default")
      (node (ref "IC1") (pin "30") (pinfunction "(XCK1)PD5_30") (pintype "bidirectional"))
    )
    (net (code "162") (name "unconnected-(IC1-AREF-Pad62)") (class "Default")
      (node (ref "IC1") (pin "62") (pinfunction "AREF_62") (pintype "passive"))
    )
    (net (code "163") (name "unconnected-(IC1-PEN-Pad1)") (class "Default")
      (node (ref "IC1") (pin "1") (pinfunction "PEN_1") (pintype "input"))
    )
    (net (code "164") (name "unconnected-(IC1-PF2(ADC2)-Pad59)") (class "Default")
      (node (ref "IC1") (pin "59") (pinfunction "PF2(ADC2)_59") (pintype "input"))
    )
    (net (code "165") (name "unconnected-(IC1-PF3(ADC3)-Pad58)") (class "Default")
      (node (ref "IC1") (pin "58") (pinfunction "PF3(ADC3)_58") (pintype "input"))
    )
    (net (code "166") (name "unconnected-(IC1-PF4(ADC4{slash}TCK)-Pad57)") (class "Default")
      (node (ref "IC1") (pin "57") (pinfunction "PF4(ADC4/TCK)_57") (pintype "input"))
    )
    (net (code "167") (name "unconnected-(IC1-PF5(ADC5{slash}TMS)-Pad56)") (class "Default")
      (node (ref "IC1") (pin "56") (pinfunction "PF5(ADC5/TMS)_56") (pintype "input"))
    )
    (net (code "168") (name "unconnected-(IC1-PF6(ADC6{slash}TDO)-Pad55)") (class "Default")
      (node (ref "IC1") (pin "55") (pinfunction "PF6(ADC6/TDO)_55") (pintype "input"))
    )
    (net (code "169") (name "unconnected-(IC1-PF7(ADC7{slash}TDI)-Pad54)") (class "Default")
      (node (ref "IC1") (pin "54") (pinfunction "PF7(ADC7/TDI)_54") (pintype "input"))
    )
    (net (code "170") (name "unconnected-(IC1-PG0(WR)-Pad33)") (class "Default")
      (node (ref "IC1") (pin "33") (pinfunction "PG0(WR)_33") (pintype "bidirectional"))
    )
    (net (code "171") (name "unconnected-(IC1-PG1(RD)-Pad34)") (class "Default")
      (node (ref "IC1") (pin "34") (pinfunction "PG1(RD)_34") (pintype "bidirectional"))
    )
    (net (code "172") (name "unconnected-(IC1-PG2(ALE)-Pad43)") (class "Default")
      (node (ref "IC1") (pin "43") (pinfunction "PG2(ALE)_43") (pintype "bidirectional"))
    )
    (net (code "173") (name "unconnected-(IC1-PG3(TOSC2)-Pad18)") (class "Default")
      (node (ref "IC1") (pin "18") (pinfunction "PG3(TOSC2)_18") (pintype "bidirectional"))
    )
    (net (code "174") (name "unconnected-(IC1-PG4(TOSC1)-Pad19)") (class "Default")
      (node (ref "IC1") (pin "19") (pinfunction "PG4(TOSC1)_19") (pintype "bidirectional"))
    )
    (net (code "175") (name "unconnected-(IC3-{slash}OUT12-Pad20)") (class "Default")
      (node (ref "IC3") (pin "20") (pinfunction "/OUT12_20") (pintype "bidirectional"))
    )
    (net (code "176") (name "unconnected-(IC3-{slash}OUT13-Pad21)") (class "Default")
      (node (ref "IC3") (pin "21") (pinfunction "/OUT13_21") (pintype "bidirectional"))
    )
    (net (code "177") (name "unconnected-(IC3-{slash}OUT14-Pad22)") (class "Default")
      (node (ref "IC3") (pin "22") (pinfunction "/OUT14_22") (pintype "bidirectional"))
    )
    (net (code "178") (name "unconnected-(IC3-{slash}OUT15-Pad23)") (class "Default")
      (node (ref "IC3") (pin "23") (pinfunction "/OUT15_23") (pintype "bidirectional"))
    )
    (net (code "179") (name "unconnected-(IC5-I{slash}O0.3-Pad7)") (class "Default")
      (node (ref "IC5") (pin "7") (pinfunction "I/O0.3_7") (pintype "bidirectional"))
    )
    (net (code "180") (name "unconnected-(IC5-I{slash}O0.4-Pad8)") (class "Default")
      (node (ref "IC5") (pin "8") (pinfunction "I/O0.4_8") (pintype "bidirectional"))
    )
    (net (code "181") (name "unconnected-(IC5-I{slash}O0.5-Pad9)") (class "Default")
      (node (ref "IC5") (pin "9") (pinfunction "I/O0.5_9") (pintype "bidirectional"))
    )
    (net (code "182") (name "unconnected-(IC6-I{slash}O0.7-Pad11)") (class "Default")
      (node (ref "IC6") (pin "11") (pinfunction "I/O0.7_11") (pintype "bidirectional"))
    )
    (net (code "183") (name "unconnected-(IC6-I{slash}O1.5-Pad18)") (class "Default")
      (node (ref "IC6") (pin "18") (pinfunction "I/O1.5_18") (pintype "bidirectional"))
    )
    (net (code "184") (name "unconnected-(IC6-I{slash}O1.6-Pad19)") (class "Default")
      (node (ref "IC6") (pin "19") (pinfunction "I/O1.6_19") (pintype "bidirectional"))
    )
    (net (code "185") (name "unconnected-(IC6-I{slash}O1.7-Pad20)") (class "Default")
      (node (ref "IC6") (pin "20") (pinfunction "I/O1.7_20") (pintype "bidirectional"))
    )
    (net (code "186") (name "unconnected-(IC8-BP3-Pad28)") (class "Default")
      (node (ref "IC8") (pin "28") (pinfunction "BP3_28") (pintype "output"))
    )
    (net (code "187") (name "unconnected-(IC8-CLK-Pad13)") (class "Default")
      (node (ref "IC8") (pin "13") (pinfunction "CLK_13") (pintype "bidirectional"))
    )
    (net (code "188") (name "unconnected-(IC8-S33-Pad64)") (class "Default")
      (node (ref "IC8") (pin "64") (pinfunction "S33_64") (pintype "output"))
    )
    (net (code "189") (name "unconnected-(IC8-S34-Pad2)") (class "Default")
      (node (ref "IC8") (pin "2") (pinfunction "S34_2") (pintype "output"))
    )
    (net (code "190") (name "unconnected-(IC8-S35-Pad3)") (class "Default")
      (node (ref "IC8") (pin "3") (pinfunction "S35_3") (pintype "output"))
    )
    (net (code "191") (name "unconnected-(IC8-S36-Pad4)") (class "Default")
      (node (ref "IC8") (pin "4") (pinfunction "S36_4") (pintype "output"))
    )
    (net (code "192") (name "unconnected-(IC8-S37-Pad5)") (class "Default")
      (node (ref "IC8") (pin "5") (pinfunction "S37_5") (pintype "output"))
    )
    (net (code "193") (name "unconnected-(IC8-S38-Pad6)") (class "Default")
      (node (ref "IC8") (pin "6") (pinfunction "S38_6") (pintype "output"))
    )
    (net (code "194") (name "unconnected-(IC8-S39-Pad7)") (class "Default")
      (node (ref "IC8") (pin "7") (pinfunction "S39_7") (pintype "output"))
    )
    (net (code "195") (name "unconnected-(IC8-SYNC-Pad12)") (class "Default")
      (node (ref "IC8") (pin "12") (pinfunction "SYNC_12") (pintype "bidirectional"))
    )
    (net (code "196") (name "unconnected-(RF-POWER-A-Pad3)") (class "Default")
      (node (ref "RF-POWER") (pin "3") (pinfunction "A_3") (pintype "passive"))
    )
  )
)
